# Custom_Keyboard.net
KiCad netlist of a schematic drawn in EasyEDA Pro
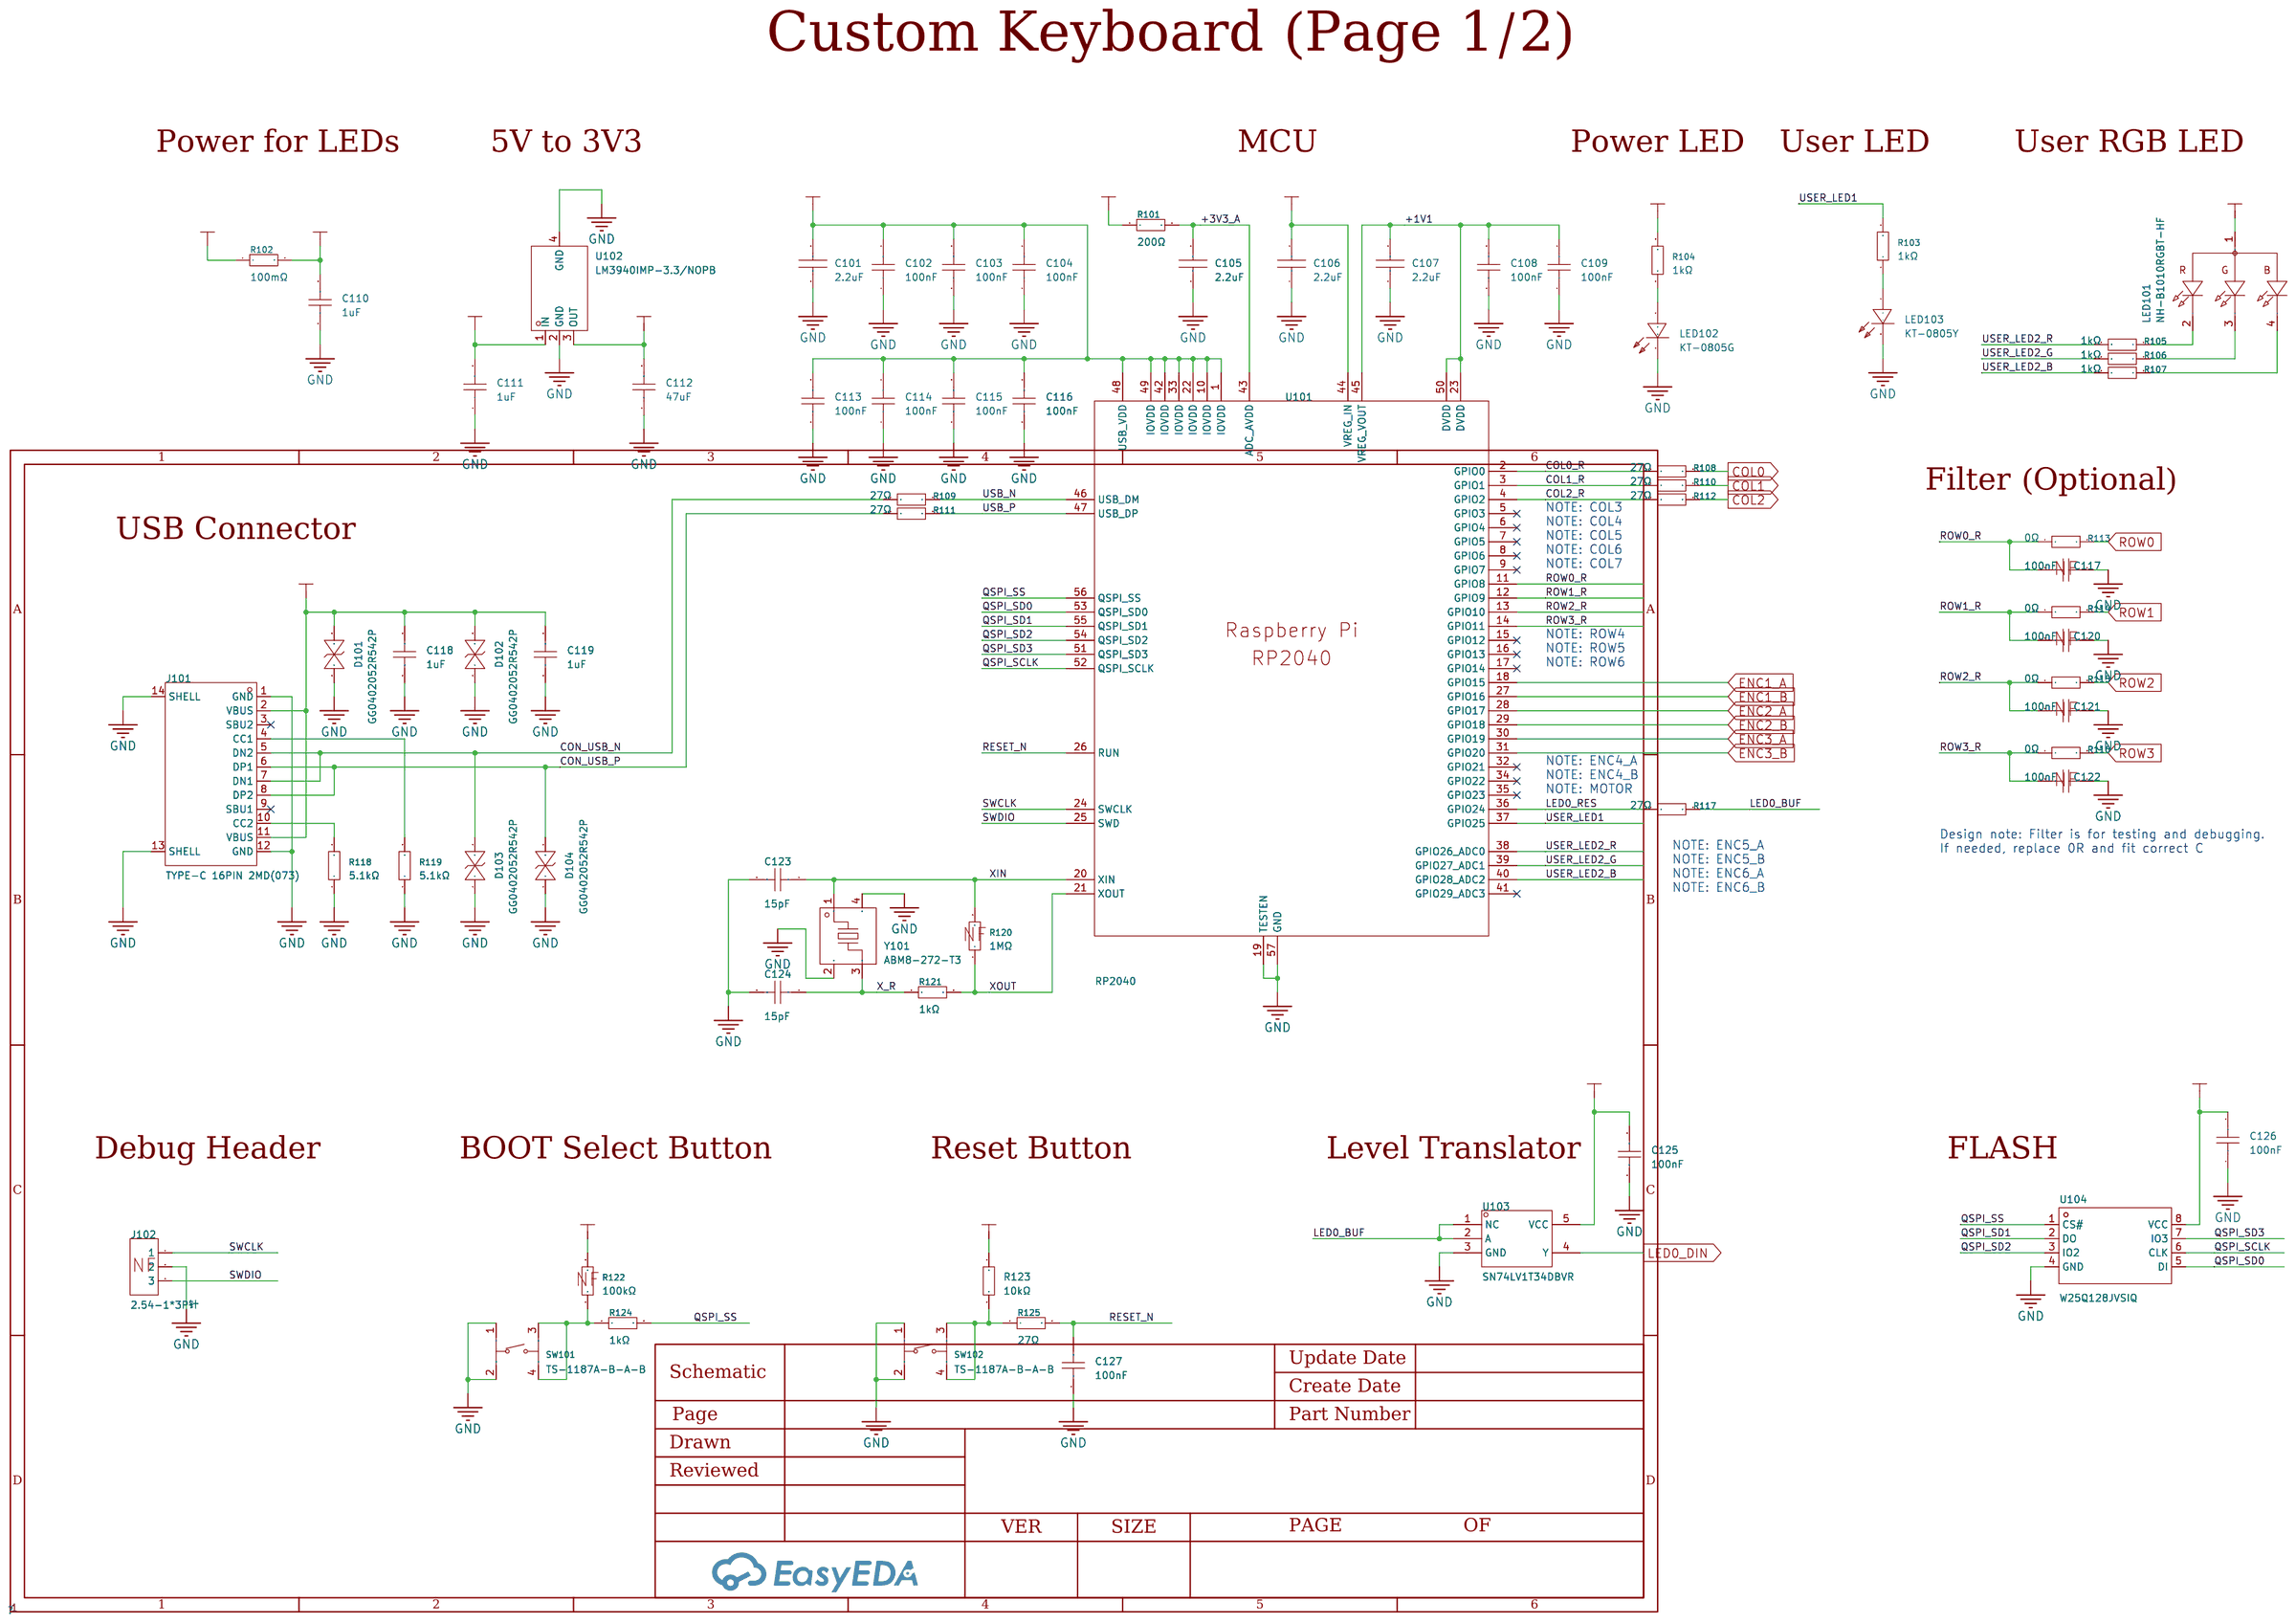
[diagram p0: MCU]
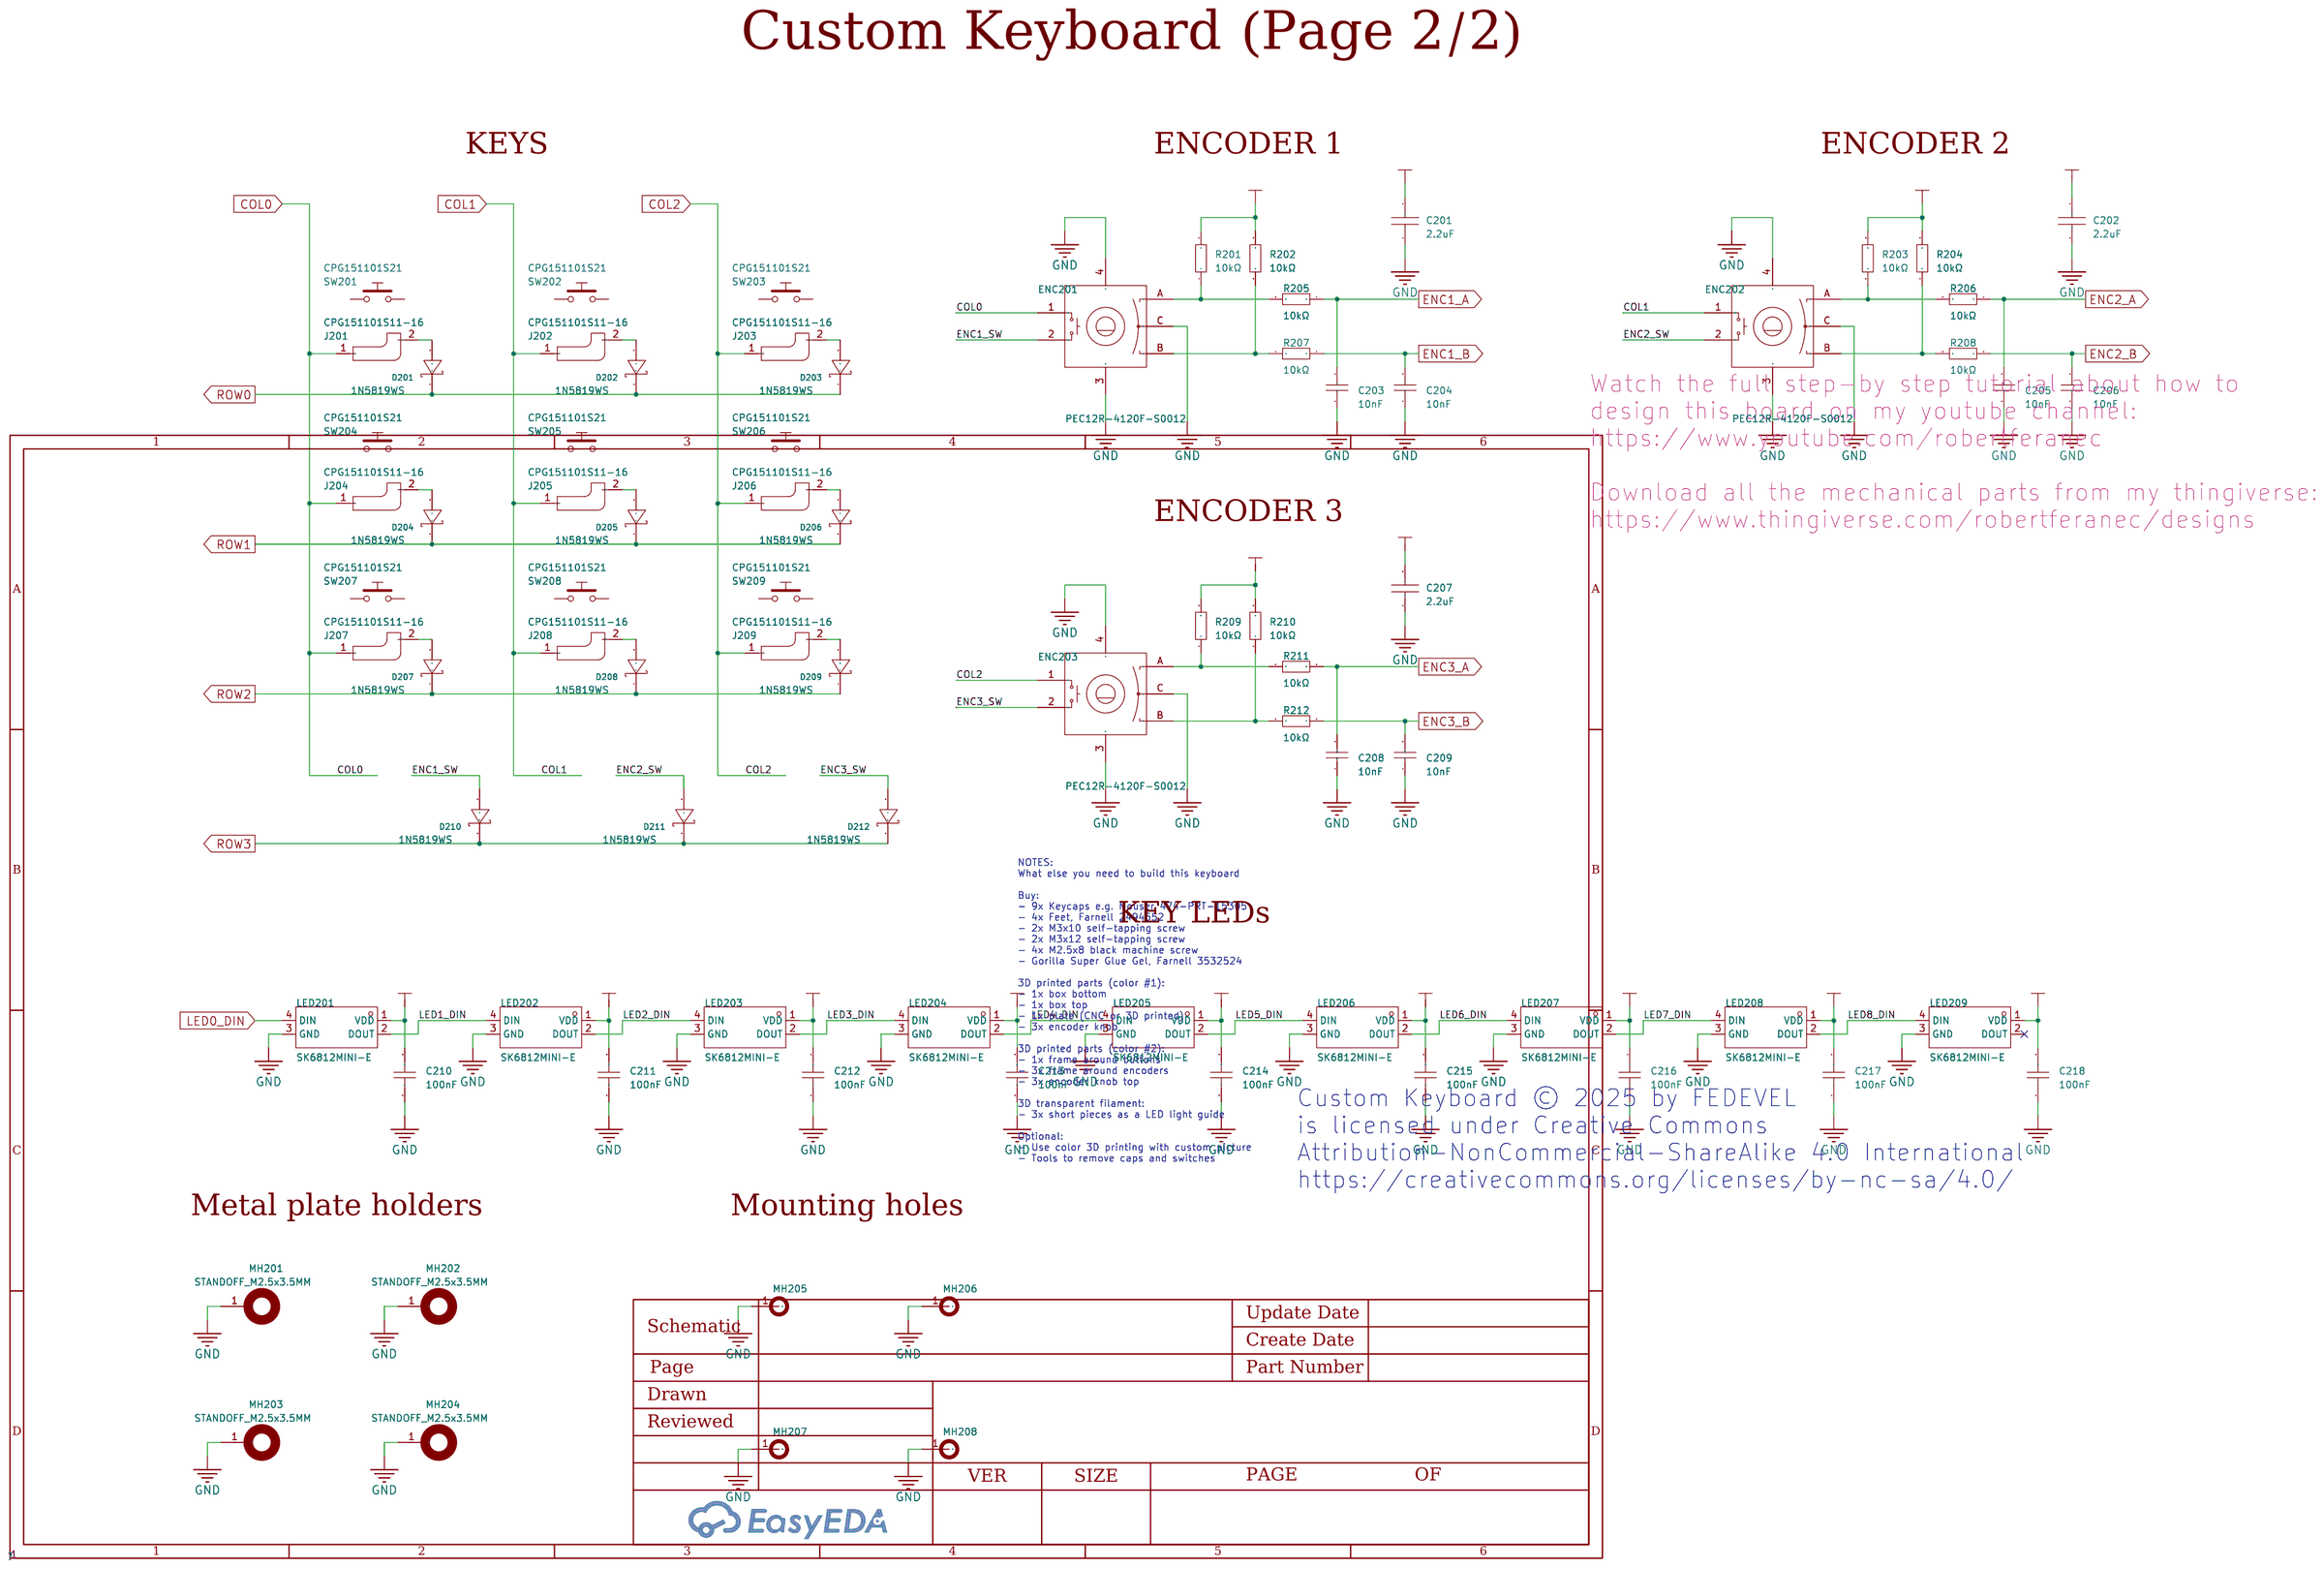
[diagram p1: OTHER]

(export (version "E")
  (design (tool "Eeschema 10.0.6"))
  (components
    (comp (ref "C101")
      (value "2.2uF")
      (footprint "easyedapro:C0402")
      (fields
        (field (name "Manufacturer Part") "CL05A225MQ5NSNC")
        (field (name "Manufacturer") "SAMSUNG(三星)")
      )
      (libsource (lib "easyedapro") (part "CL05A225MQ5NSNC"))
    )
    (comp (ref "C102")
      (value "100nF")
      (footprint "easyedapro:C0402")
      (fields
        (field (name "Manufacturer Part") "CL05B104KO5NNNC")
        (field (name "Manufacturer") "SAMSUNG(三星)")
      )
      (libsource (lib "easyedapro") (part "CL05B104KO5NNNC"))
    )
    (comp (ref "C103")
      (value "100nF")
      (footprint "easyedapro:C0402")
      (fields
        (field (name "Manufacturer Part") "CL05B104KO5NNNC")
        (field (name "Manufacturer") "SAMSUNG(三星)")
      )
      (libsource (lib "easyedapro") (part "CL05B104KO5NNNC"))
    )
    (comp (ref "C104")
      (value "100nF")
      (footprint "easyedapro:C0402")
      (fields
        (field (name "Manufacturer Part") "CL05B104KO5NNNC")
        (field (name "Manufacturer") "SAMSUNG(三星)")
      )
      (libsource (lib "easyedapro") (part "CL05B104KO5NNNC"))
    )
    (comp (ref "C105")
      (value "2.2uF")
      (footprint "easyedapro:C0402")
      (fields
        (field (name "Manufacturer Part") "CL05A225MQ5NSNC")
        (field (name "Manufacturer") "SAMSUNG(三星)")
      )
      (libsource (lib "easyedapro") (part "CL05A225MQ5NSNC"))
    )
    (comp (ref "C106")
      (value "2.2uF")
      (footprint "easyedapro:C0402")
      (fields
        (field (name "Manufacturer Part") "CL05A225MQ5NSNC")
        (field (name "Manufacturer") "SAMSUNG(三星)")
      )
      (libsource (lib "easyedapro") (part "CL05A225MQ5NSNC"))
    )
    (comp (ref "C107")
      (value "2.2uF")
      (footprint "easyedapro:C0402")
      (fields
        (field (name "Manufacturer Part") "CL05A225MQ5NSNC")
        (field (name "Manufacturer") "SAMSUNG(三星)")
      )
      (libsource (lib "easyedapro") (part "CL05A225MQ5NSNC"))
    )
    (comp (ref "C108")
      (value "100nF")
      (footprint "easyedapro:C0402")
      (fields
        (field (name "Manufacturer Part") "CL05B104KO5NNNC")
        (field (name "Manufacturer") "SAMSUNG(三星)")
      )
      (libsource (lib "easyedapro") (part "CL05B104KO5NNNC"))
    )
    (comp (ref "C109")
      (value "100nF")
      (footprint "easyedapro:C0402")
      (fields
        (field (name "Manufacturer Part") "CL05B104KO5NNNC")
        (field (name "Manufacturer") "SAMSUNG(三星)")
      )
      (libsource (lib "easyedapro") (part "CL05B104KO5NNNC"))
    )
    (comp (ref "C110")
      (value "1uF")
      (footprint "easyedapro:C0402")
      (fields
        (field (name "Manufacturer Part") "CL05A105KA5NQNC")
        (field (name "Manufacturer") "SAMSUNG(三星)")
      )
      (libsource (lib "easyedapro") (part "CL05A105KA5NQNC"))
    )
    (comp (ref "C111")
      (value "1uF")
      (footprint "easyedapro:C0402")
      (fields
        (field (name "Manufacturer Part") "CL05A105KA5NQNC")
        (field (name "Manufacturer") "SAMSUNG(三星)")
      )
      (libsource (lib "easyedapro") (part "CL05A105KA5NQNC"))
    )
    (comp (ref "C112")
      (value "47uF")
      (footprint "easyedapro:C1206")
      (fields
        (field (name "Manufacturer Part") "CL31A476MPHNNNE")
        (field (name "Manufacturer") "SAMSUNG(三星)")
      )
      (libsource (lib "easyedapro") (part "CL31A476MPHNNNE"))
    )
    (comp (ref "C113")
      (value "100nF")
      (footprint "easyedapro:C0402")
      (fields
        (field (name "Manufacturer Part") "CL05B104KO5NNNC")
        (field (name "Manufacturer") "SAMSUNG(三星)")
      )
      (libsource (lib "easyedapro") (part "CL05B104KO5NNNC"))
    )
    (comp (ref "C114")
      (value "100nF")
      (footprint "easyedapro:C0402")
      (fields
        (field (name "Manufacturer Part") "CL05B104KO5NNNC")
        (field (name "Manufacturer") "SAMSUNG(三星)")
      )
      (libsource (lib "easyedapro") (part "CL05B104KO5NNNC"))
    )
    (comp (ref "C115")
      (value "100nF")
      (footprint "easyedapro:C0402")
      (fields
        (field (name "Manufacturer Part") "CL05B104KO5NNNC")
        (field (name "Manufacturer") "SAMSUNG(三星)")
      )
      (libsource (lib "easyedapro") (part "CL05B104KO5NNNC"))
    )
    (comp (ref "C116")
      (value "100nF")
      (footprint "easyedapro:C0402")
      (fields
        (field (name "Manufacturer Part") "CL05B104KO5NNNC")
        (field (name "Manufacturer") "SAMSUNG(三星)")
      )
      (libsource (lib "easyedapro") (part "CL05B104KO5NNNC"))
    )
    (comp (ref "C117")
      (value "100nF")
      (footprint "easyedapro:C0402")
      (fields
        (field (name "Manufacturer Part") "CL05B104KO5NNNC")
        (field (name "Manufacturer") "SAMSUNG(三星)")
      )
      (libsource (lib "easyedapro") (part "CL05B104KO5NNNC"))
    )
    (comp (ref "C118")
      (value "1uF")
      (footprint "easyedapro:C0402")
      (fields
        (field (name "Manufacturer Part") "CL05A105KA5NQNC")
        (field (name "Manufacturer") "SAMSUNG(三星)")
      )
      (libsource (lib "easyedapro") (part "CL05A105KA5NQNC"))
    )
    (comp (ref "C119")
      (value "1uF")
      (footprint "easyedapro:C0402")
      (fields
        (field (name "Manufacturer Part") "CL05A105KA5NQNC")
        (field (name "Manufacturer") "SAMSUNG(三星)")
      )
      (libsource (lib "easyedapro") (part "CL05A105KA5NQNC"))
    )
    (comp (ref "C120")
      (value "100nF")
      (footprint "easyedapro:C0402")
      (fields
        (field (name "Manufacturer Part") "CL05B104KO5NNNC")
        (field (name "Manufacturer") "SAMSUNG(三星)")
      )
      (libsource (lib "easyedapro") (part "CL05B104KO5NNNC"))
    )
    (comp (ref "C121")
      (value "100nF")
      (footprint "easyedapro:C0402")
      (fields
        (field (name "Manufacturer Part") "CL05B104KO5NNNC")
        (field (name "Manufacturer") "SAMSUNG(三星)")
      )
      (libsource (lib "easyedapro") (part "CL05B104KO5NNNC"))
    )
    (comp (ref "C122")
      (value "100nF")
      (footprint "easyedapro:C0402")
      (fields
        (field (name "Manufacturer Part") "CL05B104KO5NNNC")
        (field (name "Manufacturer") "SAMSUNG(三星)")
      )
      (libsource (lib "easyedapro") (part "CL05B104KO5NNNC"))
    )
    (comp (ref "C123")
      (value "15pF")
      (footprint "easyedapro:C0402")
      (fields
        (field (name "Manufacturer Part") "CL05C150JB5NNNC")
        (field (name "Manufacturer") "SAMSUNG(三星)")
      )
      (libsource (lib "easyedapro") (part "CL05C150JB5NNNC"))
    )
    (comp (ref "C124")
      (value "15pF")
      (footprint "easyedapro:C0402")
      (fields
        (field (name "Manufacturer Part") "CL05C150JB5NNNC")
        (field (name "Manufacturer") "SAMSUNG(三星)")
      )
      (libsource (lib "easyedapro") (part "CL05C150JB5NNNC"))
    )
    (comp (ref "C125")
      (value "100nF")
      (footprint "easyedapro:C0402")
      (fields
        (field (name "Manufacturer Part") "CL05B104KO5NNNC")
        (field (name "Manufacturer") "SAMSUNG(三星)")
      )
      (libsource (lib "easyedapro") (part "CL05B104KO5NNNC"))
    )
    (comp (ref "C126")
      (value "100nF")
      (footprint "easyedapro:C0402")
      (fields
        (field (name "Manufacturer Part") "CL05B104KO5NNNC")
        (field (name "Manufacturer") "SAMSUNG(三星)")
      )
      (libsource (lib "easyedapro") (part "CL05B104KO5NNNC"))
    )
    (comp (ref "C127")
      (value "100nF")
      (footprint "easyedapro:C0402")
      (fields
        (field (name "Manufacturer Part") "CL05B104KO5NNNC")
        (field (name "Manufacturer") "SAMSUNG(三星)")
      )
      (libsource (lib "easyedapro") (part "CL05B104KO5NNNC"))
    )
    (comp (ref "D101")
      (value "GG0402052R542P")
      (footprint "easyedapro:D0402-BI")
      (fields (field (name "Manufacturer") "Kyocera AVX"))
      (libsource (lib "easyedapro") (part "GG0402052R542P"))
    )
    (comp (ref "D102")
      (value "GG0402052R542P")
      (footprint "easyedapro:D0402-BI")
      (fields (field (name "Manufacturer") "Kyocera AVX"))
      (libsource (lib "easyedapro") (part "GG0402052R542P"))
    )
    (comp (ref "D103")
      (value "GG0402052R542P")
      (footprint "easyedapro:D0402-BI")
      (fields (field (name "Manufacturer") "Kyocera AVX"))
      (libsource (lib "easyedapro") (part "GG0402052R542P"))
    )
    (comp (ref "D104")
      (value "GG0402052R542P")
      (footprint "easyedapro:D0402-BI")
      (fields (field (name "Manufacturer") "Kyocera AVX"))
      (libsource (lib "easyedapro") (part "GG0402052R542P"))
    )
    (comp (ref "J101")
      (value "TYPE-C 16PIN 2MD(073)")
      (footprint "easyedapro:USB-C-SMD_TYPE-C-6PIN-2MD-073")
      (fields (field (name "Manufacturer") "SHOU HAN(首韩)"))
      (libsource (lib "easyedapro") (part "TYPE-C 16PIN 2MD(073)"))
    )
    (comp (ref "J102")
      (value "2.54-1*3P针")
      (footprint "easyedapro:HDR-TH_3P-P2.54-V-M-1")
      (fields (field (name "Manufacturer") "BOOMELE(博穆精密)"))
      (libsource (lib "easyedapro") (part "Header-Male-2.54_1x3"))
    )
    (comp (ref "LED101")
      (value "NH-B1010RGBT-HF")
      (footprint "easyedapro:LED-ARRAY-SMD_4P-L1.0-W1.0-TR_NH-B1010RGBT_1")
      (fields (field (name "Manufacturer") "国星光电"))
      (libsource (lib "easyedapro") (part "NH-B1010RGBT-HF_RF_v1.0"))
    )
    (comp (ref "LED102")
      (value "KT-0805G")
      (footprint "easyedapro:LED0805-R-RD")
      (fields (field (name "Manufacturer") "KENTO"))
      (libsource (lib "easyedapro") (part "0805G (Green)"))
    )
    (comp (ref "LED103")
      (value "KT-0805Y")
      (footprint "easyedapro:LED0805-R-RD")
      (fields (field (name "Manufacturer") "KENTO"))
      (libsource (lib "easyedapro") (part "17-21SUYC/TR8"))
    )
    (comp (ref "R101")
      (value "200Ω")
      (footprint "easyedapro:R0402")
      (fields
        (field (name "Manufacturer Part") "0402WGF2000TCE")
        (field (name "Manufacturer") "UNI-ROYAL(厚声)")
      )
      (libsource (lib "easyedapro") (part "0402WGF2000TCE"))
    )
    (comp (ref "R102")
      (value "100mΩ")
      (footprint "easyedapro:R1206")
      (fields
        (field (name "Manufacturer Part") "1206W4F100LT5E")
        (field (name "Manufacturer") "UNI-ROYAL(厚声)")
      )
      (libsource (lib "easyedapro") (part "1206W4F100LT5E"))
    )
    (comp (ref "R103")
      (value "1kΩ")
      (footprint "easyedapro:R0402")
      (fields
        (field (name "Manufacturer Part") "0402WGF1001TCE")
        (field (name "Manufacturer") "UNI-ROYAL(厚声)")
      )
      (libsource (lib "easyedapro") (part "0402WGF1001TCE"))
    )
    (comp (ref "R104")
      (value "1kΩ")
      (footprint "easyedapro:R0402")
      (fields
        (field (name "Manufacturer Part") "0402WGF1001TCE")
        (field (name "Manufacturer") "UNI-ROYAL(厚声)")
      )
      (libsource (lib "easyedapro") (part "0402WGF1001TCE"))
    )
    (comp (ref "R105")
      (value "1kΩ")
      (footprint "easyedapro:R0402")
      (fields
        (field (name "Manufacturer Part") "0402WGF1001TCE")
        (field (name "Manufacturer") "UNI-ROYAL(厚声)")
      )
      (libsource (lib "easyedapro") (part "0402WGF1001TCE"))
    )
    (comp (ref "R106")
      (value "1kΩ")
      (footprint "easyedapro:R0402")
      (fields
        (field (name "Manufacturer Part") "0402WGF1001TCE")
        (field (name "Manufacturer") "UNI-ROYAL(厚声)")
      )
      (libsource (lib "easyedapro") (part "0402WGF1001TCE"))
    )
    (comp (ref "R107")
      (value "1kΩ")
      (footprint "easyedapro:R0402")
      (fields
        (field (name "Manufacturer Part") "0402WGF1001TCE")
        (field (name "Manufacturer") "UNI-ROYAL(厚声)")
      )
      (libsource (lib "easyedapro") (part "0402WGF1001TCE"))
    )
    (comp (ref "R108")
      (value "27Ω")
      (footprint "easyedapro:R0402")
      (fields
        (field (name "Manufacturer Part") "0402WGF270JTCE")
        (field (name "Manufacturer") "UNI-ROYAL(厚声)")
      )
      (libsource (lib "easyedapro") (part "0402WGF270JTCE"))
    )
    (comp (ref "R109")
      (value "27Ω")
      (footprint "easyedapro:R0402")
      (fields
        (field (name "Manufacturer Part") "0402WGF270JTCE")
        (field (name "Manufacturer") "UNI-ROYAL(厚声)")
      )
      (libsource (lib "easyedapro") (part "0402WGF270JTCE"))
    )
    (comp (ref "R110")
      (value "27Ω")
      (footprint "easyedapro:R0402")
      (fields
        (field (name "Manufacturer Part") "0402WGF270JTCE")
        (field (name "Manufacturer") "UNI-ROYAL(厚声)")
      )
      (libsource (lib "easyedapro") (part "0402WGF270JTCE"))
    )
    (comp (ref "R111")
      (value "27Ω")
      (footprint "easyedapro:R0402")
      (fields
        (field (name "Manufacturer Part") "0402WGF270JTCE")
        (field (name "Manufacturer") "UNI-ROYAL(厚声)")
      )
      (libsource (lib "easyedapro") (part "0402WGF270JTCE"))
    )
    (comp (ref "R112")
      (value "27Ω")
      (footprint "easyedapro:R0402")
      (fields
        (field (name "Manufacturer Part") "0402WGF270JTCE")
        (field (name "Manufacturer") "UNI-ROYAL(厚声)")
      )
      (libsource (lib "easyedapro") (part "0402WGF270JTCE"))
    )
    (comp (ref "R113")
      (value "0Ω")
      (footprint "easyedapro:R0402")
      (fields
        (field (name "Manufacturer Part") "0402WGF0000TCE")
        (field (name "Manufacturer") "UNI-ROYAL(厚声)")
      )
      (libsource (lib "easyedapro") (part "0402WGF0000TCE"))
    )
    (comp (ref "R114")
      (value "0Ω")
      (footprint "easyedapro:R0402")
      (fields
        (field (name "Manufacturer Part") "0402WGF0000TCE")
        (field (name "Manufacturer") "UNI-ROYAL(厚声)")
      )
      (libsource (lib "easyedapro") (part "0402WGF0000TCE"))
    )
    (comp (ref "R115")
      (value "0Ω")
      (footprint "easyedapro:R0402")
      (fields
        (field (name "Manufacturer Part") "0402WGF0000TCE")
        (field (name "Manufacturer") "UNI-ROYAL(厚声)")
      )
      (libsource (lib "easyedapro") (part "0402WGF0000TCE"))
    )
    (comp (ref "R116")
      (value "0Ω")
      (footprint "easyedapro:R0402")
      (fields
        (field (name "Manufacturer Part") "0402WGF0000TCE")
        (field (name "Manufacturer") "UNI-ROYAL(厚声)")
      )
      (libsource (lib "easyedapro") (part "0402WGF0000TCE"))
    )
    (comp (ref "R117")
      (value "27Ω")
      (footprint "easyedapro:R0402")
      (fields
        (field (name "Manufacturer Part") "0402WGF270JTCE")
        (field (name "Manufacturer") "UNI-ROYAL(厚声)")
      )
      (libsource (lib "easyedapro") (part "0402WGF270JTCE"))
    )
    (comp (ref "R118")
      (value "5.1kΩ")
      (footprint "easyedapro:R0402")
      (fields
        (field (name "Manufacturer Part") "0402WGF5101TCE")
        (field (name "Manufacturer") "UNI-ROYAL(厚声)")
      )
      (libsource (lib "easyedapro") (part "0402WGF5101TCE"))
    )
    (comp (ref "R119")
      (value "5.1kΩ")
      (footprint "easyedapro:R0402")
      (fields
        (field (name "Manufacturer Part") "0402WGF5101TCE")
        (field (name "Manufacturer") "UNI-ROYAL(厚声)")
      )
      (libsource (lib "easyedapro") (part "0402WGF5101TCE"))
    )
    (comp (ref "R120")
      (value "1MΩ")
      (footprint "easyedapro:R0402")
      (fields
        (field (name "Manufacturer Part") "0402WGF1004TCE")
        (field (name "Manufacturer") "UNI-ROYAL(厚声)")
      )
      (libsource (lib "easyedapro") (part "0402WGF1004TCE"))
    )
    (comp (ref "R121")
      (value "1kΩ")
      (footprint "easyedapro:R0402")
      (fields
        (field (name "Manufacturer Part") "0402WGF1001TCE")
        (field (name "Manufacturer") "UNI-ROYAL(厚声)")
      )
      (libsource (lib "easyedapro") (part "0402WGF1001TCE"))
    )
    (comp (ref "R122")
      (value "100kΩ")
      (footprint "easyedapro:R0402")
      (fields
        (field (name "Manufacturer Part") "0402WGF1003TCE")
        (field (name "Manufacturer") "UNI-ROYAL(厚声)")
      )
      (libsource (lib "easyedapro") (part "0402WGF1003TCE"))
    )
    (comp (ref "R123")
      (value "10kΩ")
      (footprint "easyedapro:R0402")
      (fields
        (field (name "Manufacturer Part") "0402WGF1002TCE")
        (field (name "Manufacturer") "UNI-ROYAL(厚声)")
      )
      (libsource (lib "easyedapro") (part "0402WGF1002TCE"))
    )
    (comp (ref "R124")
      (value "1kΩ")
      (footprint "easyedapro:R0402")
      (fields
        (field (name "Manufacturer Part") "0402WGF1001TCE")
        (field (name "Manufacturer") "UNI-ROYAL(厚声)")
      )
      (libsource (lib "easyedapro") (part "0402WGF1001TCE"))
    )
    (comp (ref "R125")
      (value "27Ω")
      (footprint "easyedapro:R0402")
      (fields
        (field (name "Manufacturer Part") "0402WGF270JTCE")
        (field (name "Manufacturer") "UNI-ROYAL(厚声)")
      )
      (libsource (lib "easyedapro") (part "0402WGF270JTCE"))
    )
    (comp (ref "SW101")
      (value "TS-1187A-B-A-B")
      (footprint "easyedapro:SW-SMD_4P-L5.1-W5.1-P3.70-LS6.5-TL-2")
      (fields (field (name "Manufacturer") "XKB Connectivity(中国星坤)"))
      (libsource (lib "easyedapro") (part "TS-1187A-B-A-B"))
    )
    (comp (ref "SW102")
      (value "TS-1187A-B-A-B")
      (footprint "easyedapro:SW-SMD_4P-L5.1-W5.1-P3.70-LS6.5-TL-2")
      (fields (field (name "Manufacturer") "XKB Connectivity(中国星坤)"))
      (libsource (lib "easyedapro") (part "TS-1187A-B-A-B"))
    )
    (comp (ref "U101")
      (value "RP2040")
      (footprint "easyedapro:LQFN-56_L7.0-W7.0-P0.4-EP_1")
      (fields (field (name "Manufacturer") "Raspberry Pi(树莓派)"))
      (libsource (lib "easyedapro") (part "RP2040_C2040_RF_v1.0"))
    )
    (comp (ref "U102")
      (value "LM3940IMP-3.3/NOPB")
      (footprint "easyedapro:SOT-223_L6.5-W3.5-P2.30-LS7.0-BR")
      (fields (field (name "Manufacturer") "TI(德州仪器)"))
      (libsource (lib "easyedapro") (part "LM3940IMP-3.3/NOPB"))
    )
    (comp (ref "U103")
      (value "SN74LV1T34DBVR")
      (footprint "easyedapro:SOT-23-5_L2.9-W1.6-P0.95-LS2.8-BR")
      (fields (field (name "Manufacturer") "TI(德州仪器)"))
      (libsource (lib "easyedapro") (part "SN74LV1T34DBVR_RF_v1.0"))
    )
    (comp (ref "U104")
      (value "W25Q128JVSIQ")
      (footprint "easyedapro:SOIC-8_L5.3-W5.3-P1.27-LS8.0-BL")
      (fields (field (name "Manufacturer") "WINBOND(华邦)"))
      (libsource (lib "easyedapro") (part "W25Q128JVSIQTR"))
    )
    (comp (ref "Y101")
      (value "ABM8-272-T3")
      (footprint "easyedapro:CRYSTAL-SMD_4P-L3.2-W2.5-BL")
      (fields (field (name "Manufacturer") "ABRACON"))
      (libsource (lib "easyedapro") (part "ABM8-272-T3_C20625731"))
    )
    (comp (ref "C201")
      (value "2.2uF")
      (footprint "easyedapro:C0402")
      (fields
        (field (name "Manufacturer Part") "CL05A225MQ5NSNC")
        (field (name "Manufacturer") "SAMSUNG(三星)")
      )
      (libsource (lib "easyedapro") (part "CL05A225MQ5NSNC"))
    )
    (comp (ref "C202")
      (value "2.2uF")
      (footprint "easyedapro:C0402")
      (fields
        (field (name "Manufacturer Part") "CL05A225MQ5NSNC")
        (field (name "Manufacturer") "SAMSUNG(三星)")
      )
      (libsource (lib "easyedapro") (part "CL05A225MQ5NSNC"))
    )
    (comp (ref "C203")
      (value "10nF")
      (footprint "easyedapro:C0402")
      (fields
        (field (name "Manufacturer Part") "CL05B103KB5NNNC")
        (field (name "Manufacturer") "SAMSUNG(三星)")
      )
      (libsource (lib "easyedapro") (part "CL05B103KB5NNNC"))
    )
    (comp (ref "C204")
      (value "10nF")
      (footprint "easyedapro:C0402")
      (fields
        (field (name "Manufacturer Part") "CL05B103KB5NNNC")
        (field (name "Manufacturer") "SAMSUNG(三星)")
      )
      (libsource (lib "easyedapro") (part "CL05B103KB5NNNC"))
    )
    (comp (ref "C205")
      (value "10nF")
      (footprint "easyedapro:C0402")
      (fields
        (field (name "Manufacturer Part") "CL05B103KB5NNNC")
        (field (name "Manufacturer") "SAMSUNG(三星)")
      )
      (libsource (lib "easyedapro") (part "CL05B103KB5NNNC"))
    )
    (comp (ref "C206")
      (value "10nF")
      (footprint "easyedapro:C0402")
      (fields
        (field (name "Manufacturer Part") "CL05B103KB5NNNC")
        (field (name "Manufacturer") "SAMSUNG(三星)")
      )
      (libsource (lib "easyedapro") (part "CL05B103KB5NNNC"))
    )
    (comp (ref "C207")
      (value "2.2uF")
      (footprint "easyedapro:C0402")
      (fields
        (field (name "Manufacturer Part") "CL05A225MQ5NSNC")
        (field (name "Manufacturer") "SAMSUNG(三星)")
      )
      (libsource (lib "easyedapro") (part "CL05A225MQ5NSNC"))
    )
    (comp (ref "C208")
      (value "10nF")
      (footprint "easyedapro:C0402")
      (fields
        (field (name "Manufacturer Part") "CL05B103KB5NNNC")
        (field (name "Manufacturer") "SAMSUNG(三星)")
      )
      (libsource (lib "easyedapro") (part "CL05B103KB5NNNC"))
    )
    (comp (ref "C209")
      (value "10nF")
      (footprint "easyedapro:C0402")
      (fields
        (field (name "Manufacturer Part") "CL05B103KB5NNNC")
        (field (name "Manufacturer") "SAMSUNG(三星)")
      )
      (libsource (lib "easyedapro") (part "CL05B103KB5NNNC"))
    )
    (comp (ref "C210")
      (value "100nF")
      (footprint "easyedapro:C0402")
      (fields
        (field (name "Manufacturer Part") "CL05B104KO5NNNC")
        (field (name "Manufacturer") "SAMSUNG(三星)")
      )
      (libsource (lib "easyedapro") (part "CL05B104KO5NNNC"))
    )
    (comp (ref "C211")
      (value "100nF")
      (footprint "easyedapro:C0402")
      (fields
        (field (name "Manufacturer Part") "CL05B104KO5NNNC")
        (field (name "Manufacturer") "SAMSUNG(三星)")
      )
      (libsource (lib "easyedapro") (part "CL05B104KO5NNNC"))
    )
    (comp (ref "C212")
      (value "100nF")
      (footprint "easyedapro:C0402")
      (fields
        (field (name "Manufacturer Part") "CL05B104KO5NNNC")
        (field (name "Manufacturer") "SAMSUNG(三星)")
      )
      (libsource (lib "easyedapro") (part "CL05B104KO5NNNC"))
    )
    (comp (ref "C213")
      (value "100nF")
      (footprint "easyedapro:C0402")
      (fields
        (field (name "Manufacturer Part") "CL05B104KO5NNNC")
        (field (name "Manufacturer") "SAMSUNG(三星)")
      )
      (libsource (lib "easyedapro") (part "CL05B104KO5NNNC"))
    )
    (comp (ref "C214")
      (value "100nF")
      (footprint "easyedapro:C0402")
      (fields
        (field (name "Manufacturer Part") "CL05B104KO5NNNC")
        (field (name "Manufacturer") "SAMSUNG(三星)")
      )
      (libsource (lib "easyedapro") (part "CL05B104KO5NNNC"))
    )
    (comp (ref "C215")
      (value "100nF")
      (footprint "easyedapro:C0402")
      (fields
        (field (name "Manufacturer Part") "CL05B104KO5NNNC")
        (field (name "Manufacturer") "SAMSUNG(三星)")
      )
      (libsource (lib "easyedapro") (part "CL05B104KO5NNNC"))
    )
    (comp (ref "C216")
      (value "100nF")
      (footprint "easyedapro:C0402")
      (fields
        (field (name "Manufacturer Part") "CL05B104KO5NNNC")
        (field (name "Manufacturer") "SAMSUNG(三星)")
      )
      (libsource (lib "easyedapro") (part "CL05B104KO5NNNC"))
    )
    (comp (ref "C217")
      (value "100nF")
      (footprint "easyedapro:C0402")
      (fields
        (field (name "Manufacturer Part") "CL05B104KO5NNNC")
        (field (name "Manufacturer") "SAMSUNG(三星)")
      )
      (libsource (lib "easyedapro") (part "CL05B104KO5NNNC"))
    )
    (comp (ref "C218")
      (value "100nF")
      (footprint "easyedapro:C0402")
      (fields
        (field (name "Manufacturer Part") "CL05B104KO5NNNC")
        (field (name "Manufacturer") "SAMSUNG(三星)")
      )
      (libsource (lib "easyedapro") (part "CL05B104KO5NNNC"))
    )
    (comp (ref "D201")
      (value "1N5819WS")
      (footprint "easyedapro:SOD-323_L1.8-W1.3-LS2.5-RD")
      (description "Forward Voltage (Vf@If):600mV@1A Reverse Voltage (Vr):40V Average Rectified Current (Io):1A")
      (fields (field (name "Manufacturer") "Hottech(合科泰)"))
      (libsource (lib "easyedapro") (part "1N5819WS"))
    )
    (comp (ref "D202")
      (value "1N5819WS")
      (footprint "easyedapro:SOD-323_L1.8-W1.3-LS2.5-RD")
      (description "Forward Voltage (Vf@If):600mV@1A Reverse Voltage (Vr):40V Average Rectified Current (Io):1A")
      (fields (field (name "Manufacturer") "Hottech(合科泰)"))
      (libsource (lib "easyedapro") (part "1N5819WS"))
    )
    (comp (ref "D203")
      (value "1N5819WS")
      (footprint "easyedapro:SOD-323_L1.8-W1.3-LS2.5-RD")
      (description "Forward Voltage (Vf@If):600mV@1A Reverse Voltage (Vr):40V Average Rectified Current (Io):1A")
      (fields (field (name "Manufacturer") "Hottech(合科泰)"))
      (libsource (lib "easyedapro") (part "1N5819WS"))
    )
    (comp (ref "D204")
      (value "1N5819WS")
      (footprint "easyedapro:SOD-323_L1.8-W1.3-LS2.5-RD")
      (description "Forward Voltage (Vf@If):600mV@1A Reverse Voltage (Vr):40V Average Rectified Current (Io):1A")
      (fields (field (name "Manufacturer") "Hottech(合科泰)"))
      (libsource (lib "easyedapro") (part "1N5819WS"))
    )
    (comp (ref "D205")
      (value "1N5819WS")
      (footprint "easyedapro:SOD-323_L1.8-W1.3-LS2.5-RD")
      (description "Forward Voltage (Vf@If):600mV@1A Reverse Voltage (Vr):40V Average Rectified Current (Io):1A")
      (fields (field (name "Manufacturer") "Hottech(合科泰)"))
      (libsource (lib "easyedapro") (part "1N5819WS"))
    )
    (comp (ref "D206")
      (value "1N5819WS")
      (footprint "easyedapro:SOD-323_L1.8-W1.3-LS2.5-RD")
      (description "Forward Voltage (Vf@If):600mV@1A Reverse Voltage (Vr):40V Average Rectified Current (Io):1A")
      (fields (field (name "Manufacturer") "Hottech(合科泰)"))
      (libsource (lib "easyedapro") (part "1N5819WS"))
    )
    (comp (ref "D207")
      (value "1N5819WS")
      (footprint "easyedapro:SOD-323_L1.8-W1.3-LS2.5-RD")
      (description "Forward Voltage (Vf@If):600mV@1A Reverse Voltage (Vr):40V Average Rectified Current (Io):1A")
      (fields (field (name "Manufacturer") "Hottech(合科泰)"))
      (libsource (lib "easyedapro") (part "1N5819WS"))
    )
    (comp (ref "D208")
      (value "1N5819WS")
      (footprint "easyedapro:SOD-323_L1.8-W1.3-LS2.5-RD")
      (description "Forward Voltage (Vf@If):600mV@1A Reverse Voltage (Vr):40V Average Rectified Current (Io):1A")
      (fields (field (name "Manufacturer") "Hottech(合科泰)"))
      (libsource (lib "easyedapro") (part "1N5819WS"))
    )
    (comp (ref "D209")
      (value "1N5819WS")
      (footprint "easyedapro:SOD-323_L1.8-W1.3-LS2.5-RD")
      (description "Forward Voltage (Vf@If):600mV@1A Reverse Voltage (Vr):40V Average Rectified Current (Io):1A")
      (fields (field (name "Manufacturer") "Hottech(合科泰)"))
      (libsource (lib "easyedapro") (part "1N5819WS"))
    )
    (comp (ref "D210")
      (value "1N5819WS")
      (footprint "easyedapro:SOD-323_L1.8-W1.3-LS2.5-RD")
      (description "Forward Voltage (Vf@If):600mV@1A Reverse Voltage (Vr):40V Average Rectified Current (Io):1A")
      (fields (field (name "Manufacturer") "Hottech(合科泰)"))
      (libsource (lib "easyedapro") (part "1N5819WS"))
    )
    (comp (ref "D211")
      (value "1N5819WS")
      (footprint "easyedapro:SOD-323_L1.8-W1.3-LS2.5-RD")
      (description "Forward Voltage (Vf@If):600mV@1A Reverse Voltage (Vr):40V Average Rectified Current (Io):1A")
      (fields (field (name "Manufacturer") "Hottech(合科泰)"))
      (libsource (lib "easyedapro") (part "1N5819WS"))
    )
    (comp (ref "D212")
      (value "1N5819WS")
      (footprint "easyedapro:SOD-323_L1.8-W1.3-LS2.5-RD")
      (description "Forward Voltage (Vf@If):600mV@1A Reverse Voltage (Vr):40V Average Rectified Current (Io):1A")
      (fields (field (name "Manufacturer") "Hottech(合科泰)"))
      (libsource (lib "easyedapro") (part "1N5819WS"))
    )
    (comp (ref "ENC201")
      (value "PEC12R-4120F-S0012")
      (footprint "easyedapro:SW-TH_PEC12R-4120F-S0012_1")
      (fields (field (name "Manufacturer") "BOURNS"))
      (libsource (lib "easyedapro") (part "PEC12R-4120F-S0012_RF_v1.0"))
    )
    (comp (ref "ENC202")
      (value "PEC12R-4120F-S0012")
      (footprint "easyedapro:SW-TH_PEC12R-4120F-S0012_1")
      (fields (field (name "Manufacturer") "BOURNS"))
      (libsource (lib "easyedapro") (part "PEC12R-4120F-S0012_RF_v1.0"))
    )
    (comp (ref "ENC203")
      (value "PEC12R-4120F-S0012")
      (footprint "easyedapro:SW-TH_PEC12R-4120F-S0012_1")
      (fields (field (name "Manufacturer") "BOURNS"))
      (libsource (lib "easyedapro") (part "PEC12R-4120F-S0012_RF_v1.0"))
    )
    (comp (ref "J201")
      (value "CPG151101S11-16")
      (footprint "easyedapro:SMD_KEYBOARD-SW_1")
      (fields (field (name "Manufacturer") "Kailh(凯华)"))
      (libsource (lib "easyedapro") (part "CPG151101S11-16_RF_v1.0"))
    )
    (comp (ref "J202")
      (value "CPG151101S11-16")
      (footprint "easyedapro:SMD_KEYBOARD-SW_1")
      (fields (field (name "Manufacturer") "Kailh(凯华)"))
      (libsource (lib "easyedapro") (part "CPG151101S11-16_RF_v1.0"))
    )
    (comp (ref "J203")
      (value "CPG151101S11-16")
      (footprint "easyedapro:SMD_KEYBOARD-SW_1")
      (fields (field (name "Manufacturer") "Kailh(凯华)"))
      (libsource (lib "easyedapro") (part "CPG151101S11-16_RF_v1.0"))
    )
    (comp (ref "J204")
      (value "CPG151101S11-16")
      (footprint "easyedapro:SMD_KEYBOARD-SW_1")
      (fields (field (name "Manufacturer") "Kailh(凯华)"))
      (libsource (lib "easyedapro") (part "CPG151101S11-16_RF_v1.0"))
    )
    (comp (ref "J205")
      (value "CPG151101S11-16")
      (footprint "easyedapro:SMD_KEYBOARD-SW_1")
      (fields (field (name "Manufacturer") "Kailh(凯华)"))
      (libsource (lib "easyedapro") (part "CPG151101S11-16_RF_v1.0"))
    )
    (comp (ref "J206")
      (value "CPG151101S11-16")
      (footprint "easyedapro:SMD_KEYBOARD-SW_1")
      (fields (field (name "Manufacturer") "Kailh(凯华)"))
      (libsource (lib "easyedapro") (part "CPG151101S11-16_RF_v1.0"))
    )
    (comp (ref "J207")
      (value "CPG151101S11-16")
      (footprint "easyedapro:SMD_KEYBOARD-SW_1")
      (fields (field (name "Manufacturer") "Kailh(凯华)"))
      (libsource (lib "easyedapro") (part "CPG151101S11-16_RF_v1.0"))
    )
    (comp (ref "J208")
      (value "CPG151101S11-16")
      (footprint "easyedapro:SMD_KEYBOARD-SW_1")
      (fields (field (name "Manufacturer") "Kailh(凯华)"))
      (libsource (lib "easyedapro") (part "CPG151101S11-16_RF_v1.0"))
    )
    (comp (ref "J209")
      (value "CPG151101S11-16")
      (footprint "easyedapro:SMD_KEYBOARD-SW_1")
      (fields (field (name "Manufacturer") "Kailh(凯华)"))
      (libsource (lib "easyedapro") (part "CPG151101S11-16_RF_v1.0"))
    )
    (comp (ref "LED201")
      (value "SK6812MINI-E")
      (footprint "easyedapro:LED-SMD_L3.2-W2.8-TR")
      (fields (field (name "Manufacturer") "欧思科光电"))
      (libsource (lib "easyedapro") (part "SK6812MINI-E_C5149201"))
    )
    (comp (ref "LED202")
      (value "SK6812MINI-E")
      (footprint "easyedapro:LED-SMD_L3.2-W2.8-TR")
      (fields (field (name "Manufacturer") "欧思科光电"))
      (libsource (lib "easyedapro") (part "SK6812MINI-E_C5149201"))
    )
    (comp (ref "LED203")
      (value "SK6812MINI-E")
      (footprint "easyedapro:LED-SMD_L3.2-W2.8-TR")
      (fields (field (name "Manufacturer") "欧思科光电"))
      (libsource (lib "easyedapro") (part "SK6812MINI-E_C5149201"))
    )
    (comp (ref "LED204")
      (value "SK6812MINI-E")
      (footprint "easyedapro:LED-SMD_L3.2-W2.8-TR")
      (fields (field (name "Manufacturer") "欧思科光电"))
      (libsource (lib "easyedapro") (part "SK6812MINI-E_C5149201"))
    )
    (comp (ref "LED205")
      (value "SK6812MINI-E")
      (footprint "easyedapro:LED-SMD_L3.2-W2.8-TR")
      (fields (field (name "Manufacturer") "欧思科光电"))
      (libsource (lib "easyedapro") (part "SK6812MINI-E_C5149201"))
    )
    (comp (ref "LED206")
      (value "SK6812MINI-E")
      (footprint "easyedapro:LED-SMD_L3.2-W2.8-TR")
      (fields (field (name "Manufacturer") "欧思科光电"))
      (libsource (lib "easyedapro") (part "SK6812MINI-E_C5149201"))
    )
    (comp (ref "LED207")
      (value "SK6812MINI-E")
      (footprint "easyedapro:LED-SMD_L3.2-W2.8-TR")
      (fields (field (name "Manufacturer") "欧思科光电"))
      (libsource (lib "easyedapro") (part "SK6812MINI-E_C5149201"))
    )
    (comp (ref "LED208")
      (value "SK6812MINI-E")
      (footprint "easyedapro:LED-SMD_L3.2-W2.8-TR")
      (fields (field (name "Manufacturer") "欧思科光电"))
      (libsource (lib "easyedapro") (part "SK6812MINI-E_C5149201"))
    )
    (comp (ref "LED209")
      (value "SK6812MINI-E")
      (footprint "easyedapro:LED-SMD_L3.2-W2.8-TR")
      (fields (field (name "Manufacturer") "欧思科光电"))
      (libsource (lib "easyedapro") (part "SK6812MINI-E_C5149201"))
    )
    (comp (ref "MH201")
      (value "STANDOFF_M2.5x3.5MM")
      (footprint "easyedapro:STANDOFF_M2.5x3.5MM_RF_v1.0")
      (description "Standoff, Steel, M2.5, Hex Female-Female, 3.5 mm, 4.9 mm, WA-SMSI Series")
      (fields (field (name "Manufacturer") "WURTH ELEKTRONIK"))
      (libsource (lib "easyedapro") (part "9774035151R_RF_v1.0"))
    )
    (comp (ref "MH202")
      (value "STANDOFF_M2.5x3.5MM")
      (footprint "easyedapro:STANDOFF_M2.5x3.5MM_RF_v1.0")
      (description "Standoff, Steel, M2.5, Hex Female-Female, 3.5 mm, 4.9 mm, WA-SMSI Series")
      (fields (field (name "Manufacturer") "WURTH ELEKTRONIK"))
      (libsource (lib "easyedapro") (part "9774035151R_RF_v1.0"))
    )
    (comp (ref "MH203")
      (value "STANDOFF_M2.5x3.5MM")
      (footprint "easyedapro:STANDOFF_M2.5x3.5MM_RF_v1.0")
      (description "Standoff, Steel, M2.5, Hex Female-Female, 3.5 mm, 4.9 mm, WA-SMSI Series")
      (fields (field (name "Manufacturer") "WURTH ELEKTRONIK"))
      (libsource (lib "easyedapro") (part "9774035151R_RF_v1.0"))
    )
    (comp (ref "MH204")
      (value "STANDOFF_M2.5x3.5MM")
      (footprint "easyedapro:STANDOFF_M2.5x3.5MM_RF_v1.0")
      (description "Standoff, Steel, M2.5, Hex Female-Female, 3.5 mm, 4.9 mm, WA-SMSI Series")
      (fields (field (name "Manufacturer") "WURTH ELEKTRONIK"))
      (libsource (lib "easyedapro") (part "9774035151R_RF_v1.0"))
    )
    (comp (ref "MH205")
      (value "~")
      (footprint "easyedapro:MH_7.5X3.2MM_RF_v1.0")
      (libsource (lib "easyedapro") (part "MH_7.5X3.2MM_RF_v1.0"))
    )
    (comp (ref "MH206")
      (value "~")
      (footprint "easyedapro:MH_7.5X3.2MM_RF_v1.0")
      (libsource (lib "easyedapro") (part "MH_7.5X3.2MM_RF_v1.0"))
    )
    (comp (ref "MH207")
      (value "~")
      (footprint "easyedapro:MH_7.5X3.2MM_RF_v1.0")
      (libsource (lib "easyedapro") (part "MH_7.5X3.2MM_RF_v1.0"))
    )
    (comp (ref "MH208")
      (value "~")
      (footprint "easyedapro:MH_7.5X3.2MM_RF_v1.0")
      (libsource (lib "easyedapro") (part "MH_7.5X3.2MM_RF_v1.0"))
    )
    (comp (ref "R201")
      (value "10kΩ")
      (footprint "easyedapro:R0402")
      (fields
        (field (name "Manufacturer Part") "0402WGF1002TCE")
        (field (name "Manufacturer") "UNI-ROYAL(厚声)")
      )
      (libsource (lib "easyedapro") (part "0402WGF1002TCE"))
    )
    (comp (ref "R202")
      (value "10kΩ")
      (footprint "easyedapro:R0402")
      (fields
        (field (name "Manufacturer Part") "0402WGF1002TCE")
        (field (name "Manufacturer") "UNI-ROYAL(厚声)")
      )
      (libsource (lib "easyedapro") (part "0402WGF1002TCE"))
    )
    (comp (ref "R203")
      (value "10kΩ")
      (footprint "easyedapro:R0402")
      (fields
        (field (name "Manufacturer Part") "0402WGF1002TCE")
        (field (name "Manufacturer") "UNI-ROYAL(厚声)")
      )
      (libsource (lib "easyedapro") (part "0402WGF1002TCE"))
    )
    (comp (ref "R204")
      (value "10kΩ")
      (footprint "easyedapro:R0402")
      (fields
        (field (name "Manufacturer Part") "0402WGF1002TCE")
        (field (name "Manufacturer") "UNI-ROYAL(厚声)")
      )
      (libsource (lib "easyedapro") (part "0402WGF1002TCE"))
    )
    (comp (ref "R205")
      (value "10kΩ")
      (footprint "easyedapro:R0402")
      (fields
        (field (name "Manufacturer Part") "0402WGF1002TCE")
        (field (name "Manufacturer") "UNI-ROYAL(厚声)")
      )
      (libsource (lib "easyedapro") (part "0402WGF1002TCE"))
    )
    (comp (ref "R206")
      (value "10kΩ")
      (footprint "easyedapro:R0402")
      (fields
        (field (name "Manufacturer Part") "0402WGF1002TCE")
        (field (name "Manufacturer") "UNI-ROYAL(厚声)")
      )
      (libsource (lib "easyedapro") (part "0402WGF1002TCE"))
    )
    (comp (ref "R207")
      (value "10kΩ")
      (footprint "easyedapro:R0402")
      (fields
        (field (name "Manufacturer Part") "0402WGF1002TCE")
        (field (name "Manufacturer") "UNI-ROYAL(厚声)")
      )
      (libsource (lib "easyedapro") (part "0402WGF1002TCE"))
    )
    (comp (ref "R208")
      (value "10kΩ")
      (footprint "easyedapro:R0402")
      (fields
        (field (name "Manufacturer Part") "0402WGF1002TCE")
        (field (name "Manufacturer") "UNI-ROYAL(厚声)")
      )
      (libsource (lib "easyedapro") (part "0402WGF1002TCE"))
    )
    (comp (ref "R209")
      (value "10kΩ")
      (footprint "easyedapro:R0402")
      (fields
        (field (name "Manufacturer Part") "0402WGF1002TCE")
        (field (name "Manufacturer") "UNI-ROYAL(厚声)")
      )
      (libsource (lib "easyedapro") (part "0402WGF1002TCE"))
    )
    (comp (ref "R210")
      (value "10kΩ")
      (footprint "easyedapro:R0402")
      (fields
        (field (name "Manufacturer Part") "0402WGF1002TCE")
        (field (name "Manufacturer") "UNI-ROYAL(厚声)")
      )
      (libsource (lib "easyedapro") (part "0402WGF1002TCE"))
    )
    (comp (ref "R211")
      (value "10kΩ")
      (footprint "easyedapro:R0402")
      (fields
        (field (name "Manufacturer Part") "0402WGF1002TCE")
        (field (name "Manufacturer") "UNI-ROYAL(厚声)")
      )
      (libsource (lib "easyedapro") (part "0402WGF1002TCE"))
    )
    (comp (ref "R212")
      (value "10kΩ")
      (footprint "easyedapro:R0402")
      (fields
        (field (name "Manufacturer Part") "0402WGF1002TCE")
        (field (name "Manufacturer") "UNI-ROYAL(厚声)")
      )
      (libsource (lib "easyedapro") (part "0402WGF1002TCE"))
    )
    (comp (ref "SW201")
      (value "CPG151101S21")
      (footprint "easyedapro:KEY-TH_CPG1511F01S0X_1")
      (fields (field (name "Manufacturer") "Kailh(凯华)"))
      (libsource (lib "easyedapro") (part "CPG151101S21 RF v1.0"))
    )
    (comp (ref "SW202")
      (value "CPG151101S21")
      (footprint "easyedapro:KEY-TH_CPG1511F01S0X_1")
      (fields (field (name "Manufacturer") "Kailh(凯华)"))
      (libsource (lib "easyedapro") (part "CPG151101S21 RF v1.0"))
    )
    (comp (ref "SW203")
      (value "CPG151101S21")
      (footprint "easyedapro:KEY-TH_CPG1511F01S0X_1")
      (fields (field (name "Manufacturer") "Kailh(凯华)"))
      (libsource (lib "easyedapro") (part "CPG151101S21 RF v1.0"))
    )
    (comp (ref "SW204")
      (value "CPG151101S21")
      (footprint "easyedapro:KEY-TH_CPG1511F01S0X_1")
      (fields (field (name "Manufacturer") "Kailh(凯华)"))
      (libsource (lib "easyedapro") (part "CPG151101S21 RF v1.0"))
    )
    (comp (ref "SW205")
      (value "CPG151101S21")
      (footprint "easyedapro:KEY-TH_CPG1511F01S0X_1")
      (fields (field (name "Manufacturer") "Kailh(凯华)"))
      (libsource (lib "easyedapro") (part "CPG151101S21 RF v1.0"))
    )
    (comp (ref "SW206")
      (value "CPG151101S21")
      (footprint "easyedapro:KEY-TH_CPG1511F01S0X_1")
      (fields (field (name "Manufacturer") "Kailh(凯华)"))
      (libsource (lib "easyedapro") (part "CPG151101S21 RF v1.0"))
    )
    (comp (ref "SW207")
      (value "CPG151101S21")
      (footprint "easyedapro:KEY-TH_CPG1511F01S0X_1")
      (fields (field (name "Manufacturer") "Kailh(凯华)"))
      (libsource (lib "easyedapro") (part "CPG151101S21 RF v1.0"))
    )
    (comp (ref "SW208")
      (value "CPG151101S21")
      (footprint "easyedapro:KEY-TH_CPG1511F01S0X_1")
      (fields (field (name "Manufacturer") "Kailh(凯华)"))
      (libsource (lib "easyedapro") (part "CPG151101S21 RF v1.0"))
    )
    (comp (ref "SW209")
      (value "CPG151101S21")
      (footprint "easyedapro:KEY-TH_CPG1511F01S0X_1")
      (fields (field (name "Manufacturer") "Kailh(凯华)"))
      (libsource (lib "easyedapro") (part "CPG151101S21 RF v1.0"))
    )
  )
  (nets
    (net (code "1") (name "+1V1") (class "Default")
      (node (ref "C107") (pin "2") (pinfunction "2_2") (pintype "unspecified"))
      (node (ref "C108") (pin "2") (pinfunction "2_2") (pintype "unspecified"))
      (node (ref "C109") (pin "2") (pinfunction "2_2") (pintype "unspecified"))
      (node (ref "U101") (pin "23") (pinfunction "DVDD_23") (pintype "bidirectional"))
      (node (ref "U101") (pin "45") (pinfunction "VREG_VOUT_45") (pintype "bidirectional"))
      (node (ref "U101") (pin "50") (pinfunction "DVDD_50") (pintype "bidirectional"))
    )
    (net (code "2") (name "+3V3") (class "Default")
      (node (ref "C101") (pin "2") (pinfunction "2_2") (pintype "unspecified"))
      (node (ref "C102") (pin "2") (pinfunction "2_2") (pintype "unspecified"))
      (node (ref "C103") (pin "2") (pinfunction "2_2") (pintype "unspecified"))
      (node (ref "C104") (pin "2") (pinfunction "2_2") (pintype "unspecified"))
      (node (ref "C106") (pin "2") (pinfunction "2_2") (pintype "unspecified"))
      (node (ref "C112") (pin "2") (pinfunction "2_2") (pintype "unspecified"))
      (node (ref "C113") (pin "2") (pinfunction "2_2") (pintype "unspecified"))
      (node (ref "C114") (pin "2") (pinfunction "2_2") (pintype "unspecified"))
      (node (ref "C115") (pin "2") (pinfunction "2_2") (pintype "unspecified"))
      (node (ref "C116") (pin "2") (pinfunction "2_2") (pintype "unspecified"))
      (node (ref "C126") (pin "2") (pinfunction "2_2") (pintype "unspecified"))
      (node (ref "C201") (pin "2") (pinfunction "2_2") (pintype "unspecified"))
      (node (ref "C202") (pin "2") (pinfunction "2_2") (pintype "unspecified"))
      (node (ref "C207") (pin "2") (pinfunction "2_2") (pintype "unspecified"))
      (node (ref "LED101") (pin "1") (pinfunction "+_1") (pintype "unspecified"))
      (node (ref "R101") (pin "1") (pinfunction "1_1") (pintype "input"))
      (node (ref "R104") (pin "2") (pinfunction "2_2") (pintype "input"))
      (node (ref "R122") (pin "2") (pinfunction "2_2") (pintype "input"))
      (node (ref "R123") (pin "2") (pinfunction "2_2") (pintype "input"))
      (node (ref "R201") (pin "2") (pinfunction "2_2") (pintype "input"))
      (node (ref "R202") (pin "2") (pinfunction "2_2") (pintype "input"))
      (node (ref "R203") (pin "2") (pinfunction "2_2") (pintype "input"))
      (node (ref "R204") (pin "2") (pinfunction "2_2") (pintype "input"))
      (node (ref "R209") (pin "2") (pinfunction "2_2") (pintype "input"))
      (node (ref "R210") (pin "2") (pinfunction "2_2") (pintype "input"))
      (node (ref "U101") (pin "1") (pinfunction "IOVDD_1") (pintype "bidirectional"))
      (node (ref "U101") (pin "10") (pinfunction "IOVDD_10") (pintype "bidirectional"))
      (node (ref "U101") (pin "22") (pinfunction "IOVDD_22") (pintype "bidirectional"))
      (node (ref "U101") (pin "33") (pinfunction "IOVDD_33") (pintype "bidirectional"))
      (node (ref "U101") (pin "42") (pinfunction "IOVDD_42") (pintype "bidirectional"))
      (node (ref "U101") (pin "44") (pinfunction "VREG_IN_44") (pintype "bidirectional"))
      (node (ref "U101") (pin "48") (pinfunction "USB_VDD_48") (pintype "bidirectional"))
      (node (ref "U101") (pin "49") (pinfunction "IOVDD_49") (pintype "bidirectional"))
      (node (ref "U102") (pin "3") (pinfunction "OUT_3") (pintype "unspecified"))
      (node (ref "U104") (pin "8") (pinfunction "VCC_8") (pintype "unspecified"))
    )
    (net (code "3") (name "+3V3_A") (class "Default")
      (node (ref "C105") (pin "2") (pinfunction "2_2") (pintype "unspecified"))
      (node (ref "R101") (pin "2") (pinfunction "2_2") (pintype "input"))
      (node (ref "U101") (pin "43") (pinfunction "ADC_AVDD_43") (pintype "bidirectional"))
    )
    (net (code "4") (name "+5V_LEDS") (class "Default")
      (node (ref "C110") (pin "2") (pinfunction "2_2") (pintype "unspecified"))
      (node (ref "C210") (pin "2") (pinfunction "2_2") (pintype "unspecified"))
      (node (ref "C211") (pin "2") (pinfunction "2_2") (pintype "unspecified"))
      (node (ref "C212") (pin "2") (pinfunction "2_2") (pintype "unspecified"))
      (node (ref "C213") (pin "2") (pinfunction "2_2") (pintype "unspecified"))
      (node (ref "C214") (pin "2") (pinfunction "2_2") (pintype "unspecified"))
      (node (ref "C215") (pin "2") (pinfunction "2_2") (pintype "unspecified"))
      (node (ref "C216") (pin "2") (pinfunction "2_2") (pintype "unspecified"))
      (node (ref "C217") (pin "2") (pinfunction "2_2") (pintype "unspecified"))
      (node (ref "C218") (pin "2") (pinfunction "2_2") (pintype "unspecified"))
      (node (ref "LED201") (pin "1") (pinfunction "VDD_1") (pintype "unspecified"))
      (node (ref "LED202") (pin "1") (pinfunction "VDD_1") (pintype "unspecified"))
      (node (ref "LED203") (pin "1") (pinfunction "VDD_1") (pintype "unspecified"))
      (node (ref "LED204") (pin "1") (pinfunction "VDD_1") (pintype "unspecified"))
      (node (ref "LED205") (pin "1") (pinfunction "VDD_1") (pintype "unspecified"))
      (node (ref "LED206") (pin "1") (pinfunction "VDD_1") (pintype "unspecified"))
      (node (ref "LED207") (pin "1") (pinfunction "VDD_1") (pintype "unspecified"))
      (node (ref "LED208") (pin "1") (pinfunction "VDD_1") (pintype "unspecified"))
      (node (ref "LED209") (pin "1") (pinfunction "VDD_1") (pintype "unspecified"))
      (node (ref "R102") (pin "2") (pinfunction "2_2") (pintype "input"))
    )
    (net (code "5") (name "+5V_USB") (class "Default")
      (node (ref "C111") (pin "2") (pinfunction "2_2") (pintype "unspecified"))
      (node (ref "C118") (pin "2") (pinfunction "2_2") (pintype "unspecified"))
      (node (ref "C119") (pin "2") (pinfunction "2_2") (pintype "unspecified"))
      (node (ref "C125") (pin "2") (pinfunction "2_2") (pintype "unspecified"))
      (node (ref "D101") (pin "2") (pinfunction "2_2") (pintype "input"))
      (node (ref "D102") (pin "2") (pinfunction "2_2") (pintype "input"))
      (node (ref "J101") (pin "11") (pinfunction "VBUS_11") (pintype "unspecified"))
      (node (ref "J101") (pin "2") (pinfunction "VBUS_2") (pintype "unspecified"))
      (node (ref "R102") (pin "1") (pinfunction "1_1") (pintype "input"))
      (node (ref "U102") (pin "1") (pinfunction "IN_1") (pintype "unspecified"))
      (node (ref "U103") (pin "5") (pinfunction "VCC_5") (pintype "unspecified"))
    )
    (net (code "6") (name "COL0") (class "Default")
      (node (ref "ENC201") (pin "1") (pinfunction "1_1") (pintype "input"))
      (node (ref "J201") (pin "1") (pinfunction "1_1") (pintype "input"))
      (node (ref "J204") (pin "1") (pinfunction "1_1") (pintype "input"))
      (node (ref "J207") (pin "1") (pinfunction "1_1") (pintype "input"))
      (node (ref "R108") (pin "2") (pinfunction "2_2") (pintype "input"))
    )
    (net (code "7") (name "COL0_R") (class "Default")
      (node (ref "R108") (pin "1") (pinfunction "1_1") (pintype "input"))
      (node (ref "U101") (pin "2") (pinfunction "GPIO0_2") (pintype "bidirectional"))
    )
    (net (code "8") (name "COL1") (class "Default")
      (node (ref "ENC202") (pin "1") (pinfunction "1_1") (pintype "input"))
      (node (ref "J202") (pin "1") (pinfunction "1_1") (pintype "input"))
      (node (ref "J205") (pin "1") (pinfunction "1_1") (pintype "input"))
      (node (ref "J208") (pin "1") (pinfunction "1_1") (pintype "input"))
      (node (ref "R110") (pin "2") (pinfunction "2_2") (pintype "input"))
    )
    (net (code "9") (name "COL1_R") (class "Default")
      (node (ref "R110") (pin "1") (pinfunction "1_1") (pintype "input"))
      (node (ref "U101") (pin "3") (pinfunction "GPIO1_3") (pintype "bidirectional"))
    )
    (net (code "10") (name "COL2") (class "Default")
      (node (ref "ENC203") (pin "1") (pinfunction "1_1") (pintype "input"))
      (node (ref "J203") (pin "1") (pinfunction "1_1") (pintype "input"))
      (node (ref "J206") (pin "1") (pinfunction "1_1") (pintype "input"))
      (node (ref "J209") (pin "1") (pinfunction "1_1") (pintype "input"))
      (node (ref "R112") (pin "2") (pinfunction "2_2") (pintype "input"))
    )
    (net (code "11") (name "COL2_R") (class "Default")
      (node (ref "R112") (pin "1") (pinfunction "1_1") (pintype "input"))
      (node (ref "U101") (pin "4") (pinfunction "GPIO2_4") (pintype "bidirectional"))
    )
    (net (code "12") (name "CON_USB_N") (class "Default")
      (node (ref "D103") (pin "2") (pinfunction "2_2") (pintype "input"))
      (node (ref "J101") (pin "5") (pinfunction "DN2_5") (pintype "unspecified"))
      (node (ref "J101") (pin "7") (pinfunction "DN1_7") (pintype "unspecified"))
      (node (ref "R109") (pin "1") (pinfunction "1_1") (pintype "input"))
    )
    (net (code "13") (name "CON_USB_P") (class "Default")
      (node (ref "D104") (pin "2") (pinfunction "2_2") (pintype "input"))
      (node (ref "J101") (pin "6") (pinfunction "DP1_6") (pintype "unspecified"))
      (node (ref "J101") (pin "8") (pinfunction "DP2_8") (pintype "unspecified"))
      (node (ref "R111") (pin "1") (pinfunction "1_1") (pintype "input"))
    )
    (net (code "14") (name "ENC1_A") (class "Default")
      (node (ref "C203") (pin "2") (pinfunction "2_2") (pintype "input"))
      (node (ref "R205") (pin "1") (pinfunction "1_1") (pintype "input"))
      (node (ref "U101") (pin "18") (pinfunction "GPIO15_18") (pintype "bidirectional"))
    )
    (net (code "15") (name "ENC1_B") (class "Default")
      (node (ref "C204") (pin "2") (pinfunction "2_2") (pintype "input"))
      (node (ref "R207") (pin "1") (pinfunction "1_1") (pintype "input"))
      (node (ref "U101") (pin "27") (pinfunction "GPIO16_27") (pintype "bidirectional"))
    )
    (net (code "16") (name "ENC1_SW") (class "Default")
      (node (ref "D210") (pin "2") (pinfunction "A_2") (pintype "input"))
      (node (ref "ENC201") (pin "2") (pinfunction "2_2") (pintype "input"))
    )
    (net (code "17") (name "ENC2_A") (class "Default")
      (node (ref "C205") (pin "2") (pinfunction "2_2") (pintype "input"))
      (node (ref "R206") (pin "1") (pinfunction "1_1") (pintype "input"))
      (node (ref "U101") (pin "28") (pinfunction "GPIO17_28") (pintype "bidirectional"))
    )
    (net (code "18") (name "ENC2_B") (class "Default")
      (node (ref "C206") (pin "2") (pinfunction "2_2") (pintype "input"))
      (node (ref "R208") (pin "1") (pinfunction "1_1") (pintype "input"))
      (node (ref "U101") (pin "29") (pinfunction "GPIO18_29") (pintype "bidirectional"))
    )
    (net (code "19") (name "ENC2_SW") (class "Default")
      (node (ref "D211") (pin "2") (pinfunction "A_2") (pintype "input"))
      (node (ref "ENC202") (pin "2") (pinfunction "2_2") (pintype "input"))
    )
    (net (code "20") (name "ENC3_A") (class "Default")
      (node (ref "C208") (pin "2") (pinfunction "2_2") (pintype "input"))
      (node (ref "R211") (pin "1") (pinfunction "1_1") (pintype "input"))
      (node (ref "U101") (pin "30") (pinfunction "GPIO19_30") (pintype "bidirectional"))
    )
    (net (code "21") (name "ENC3_B") (class "Default")
      (node (ref "C209") (pin "2") (pinfunction "2_2") (pintype "input"))
      (node (ref "R212") (pin "1") (pinfunction "1_1") (pintype "input"))
      (node (ref "U101") (pin "31") (pinfunction "GPIO20_31") (pintype "bidirectional"))
    )
    (net (code "22") (name "ENC3_SW") (class "Default")
      (node (ref "D212") (pin "2") (pinfunction "A_2") (pintype "input"))
      (node (ref "ENC203") (pin "2") (pinfunction "2_2") (pintype "input"))
    )
    (net (code "23") (name "GND") (class "Default")
      (node (ref "C101") (pin "1") (pinfunction "1_1") (pintype "unspecified"))
      (node (ref "C102") (pin "1") (pinfunction "1_1") (pintype "unspecified"))
      (node (ref "C103") (pin "1") (pinfunction "1_1") (pintype "unspecified"))
      (node (ref "C104") (pin "1") (pinfunction "1_1") (pintype "unspecified"))
      (node (ref "C105") (pin "1") (pinfunction "1_1") (pintype "unspecified"))
      (node (ref "C106") (pin "1") (pinfunction "1_1") (pintype "unspecified"))
      (node (ref "C107") (pin "1") (pinfunction "1_1") (pintype "unspecified"))
      (node (ref "C108") (pin "1") (pinfunction "1_1") (pintype "unspecified"))
      (node (ref "C109") (pin "1") (pinfunction "1_1") (pintype "unspecified"))
      (node (ref "C110") (pin "1") (pinfunction "1_1") (pintype "unspecified"))
      (node (ref "C111") (pin "1") (pinfunction "1_1") (pintype "unspecified"))
      (node (ref "C112") (pin "1") (pinfunction "1_1") (pintype "unspecified"))
      (node (ref "C113") (pin "1") (pinfunction "1_1") (pintype "unspecified"))
      (node (ref "C114") (pin "1") (pinfunction "1_1") (pintype "unspecified"))
      (node (ref "C115") (pin "1") (pinfunction "1_1") (pintype "unspecified"))
      (node (ref "C116") (pin "1") (pinfunction "1_1") (pintype "unspecified"))
      (node (ref "C117") (pin "1") (pinfunction "1_1") (pintype "unspecified"))
      (node (ref "C118") (pin "1") (pinfunction "1_1") (pintype "unspecified"))
      (node (ref "C119") (pin "1") (pinfunction "1_1") (pintype "unspecified"))
      (node (ref "C120") (pin "1") (pinfunction "1_1") (pintype "unspecified"))
      (node (ref "C121") (pin "1") (pinfunction "1_1") (pintype "unspecified"))
      (node (ref "C122") (pin "1") (pinfunction "1_1") (pintype "unspecified"))
      (node (ref "C123") (pin "2") (pinfunction "2_2") (pintype "unspecified"))
      (node (ref "C124") (pin "2") (pinfunction "2_2") (pintype "unspecified"))
      (node (ref "C125") (pin "1") (pinfunction "1_1") (pintype "unspecified"))
      (node (ref "C126") (pin "1") (pinfunction "1_1") (pintype "unspecified"))
      (node (ref "C127") (pin "1") (pinfunction "1_1") (pintype "unspecified"))
      (node (ref "C201") (pin "1") (pinfunction "1_1") (pintype "unspecified"))
      (node (ref "C202") (pin "1") (pinfunction "1_1") (pintype "unspecified"))
      (node (ref "C203") (pin "1") (pinfunction "1_1") (pintype "input"))
      (node (ref "C204") (pin "1") (pinfunction "1_1") (pintype "input"))
      (node (ref "C205") (pin "1") (pinfunction "1_1") (pintype "input"))
      (node (ref "C206") (pin "1") (pinfunction "1_1") (pintype "input"))
      (node (ref "C207") (pin "1") (pinfunction "1_1") (pintype "unspecified"))
      (node (ref "C208") (pin "1") (pinfunction "1_1") (pintype "input"))
      (node (ref "C209") (pin "1") (pinfunction "1_1") (pintype "input"))
      (node (ref "C210") (pin "1") (pinfunction "1_1") (pintype "unspecified"))
      (node (ref "C211") (pin "1") (pinfunction "1_1") (pintype "unspecified"))
      (node (ref "C212") (pin "1") (pinfunction "1_1") (pintype "unspecified"))
      (node (ref "C213") (pin "1") (pinfunction "1_1") (pintype "unspecified"))
      (node (ref "C214") (pin "1") (pinfunction "1_1") (pintype "unspecified"))
      (node (ref "C215") (pin "1") (pinfunction "1_1") (pintype "unspecified"))
      (node (ref "C216") (pin "1") (pinfunction "1_1") (pintype "unspecified"))
      (node (ref "C217") (pin "1") (pinfunction "1_1") (pintype "unspecified"))
      (node (ref "C218") (pin "1") (pinfunction "1_1") (pintype "unspecified"))
      (node (ref "D101") (pin "1") (pinfunction "1_1") (pintype "input"))
      (node (ref "D102") (pin "1") (pinfunction "1_1") (pintype "input"))
      (node (ref "D103") (pin "1") (pinfunction "1_1") (pintype "input"))
      (node (ref "D104") (pin "1") (pinfunction "1_1") (pintype "input"))
      (node (ref "ENC201") (pin "3") (pinfunction "3_3") (pintype "input"))
      (node (ref "ENC201") (pin "4") (pinfunction "4_4") (pintype "input"))
      (node (ref "ENC201") (pin "C") (pinfunction "C_C") (pintype "input"))
      (node (ref "ENC202") (pin "3") (pinfunction "3_3") (pintype "input"))
      (node (ref "ENC202") (pin "4") (pinfunction "4_4") (pintype "input"))
      (node (ref "ENC202") (pin "C") (pinfunction "C_C") (pintype "input"))
      (node (ref "ENC203") (pin "3") (pinfunction "3_3") (pintype "input"))
      (node (ref "ENC203") (pin "4") (pinfunction "4_4") (pintype "input"))
      (node (ref "ENC203") (pin "C") (pinfunction "C_C") (pintype "input"))
      (node (ref "J101") (pin "1") (pinfunction "GND_1") (pintype "unspecified"))
      (node (ref "J101") (pin "12") (pinfunction "GND_12") (pintype "unspecified"))
      (node (ref "J101") (pin "13") (pinfunction "SHELL_13") (pintype "unspecified"))
      (node (ref "J101") (pin "14") (pinfunction "SHELL_14") (pintype "unspecified"))
      (node (ref "J102") (pin "2") (pinfunction "2_2") (pintype "input"))
      (node (ref "LED102") (pin "2") (pinfunction "K_2") (pintype "unspecified"))
      (node (ref "LED103") (pin "2") (pinfunction "-_2") (pintype "unspecified"))
      (node (ref "LED201") (pin "3") (pinfunction "GND_3") (pintype "unspecified"))
      (node (ref "LED202") (pin "3") (pinfunction "GND_3") (pintype "unspecified"))
      (node (ref "LED203") (pin "3") (pinfunction "GND_3") (pintype "unspecified"))
      (node (ref "LED204") (pin "3") (pinfunction "GND_3") (pintype "unspecified"))
      (node (ref "LED205") (pin "3") (pinfunction "GND_3") (pintype "unspecified"))
      (node (ref "LED206") (pin "3") (pinfunction "GND_3") (pintype "unspecified"))
      (node (ref "LED207") (pin "3") (pinfunction "GND_3") (pintype "unspecified"))
      (node (ref "LED208") (pin "3") (pinfunction "GND_3") (pintype "unspecified"))
      (node (ref "LED209") (pin "3") (pinfunction "GND_3") (pintype "unspecified"))
      (node (ref "MH201") (pin "1") (pinfunction "1_1") (pintype "input"))
      (node (ref "MH202") (pin "1") (pinfunction "1_1") (pintype "input"))
      (node (ref "MH203") (pin "1") (pinfunction "1_1") (pintype "input"))
      (node (ref "MH204") (pin "1") (pinfunction "1_1") (pintype "input"))
      (node (ref "MH205") (pin "1") (pinfunction "1_1") (pintype "input"))
      (node (ref "MH206") (pin "1") (pinfunction "1_1") (pintype "input"))
      (node (ref "MH207") (pin "1") (pinfunction "1_1") (pintype "input"))
      (node (ref "MH208") (pin "1") (pinfunction "1_1") (pintype "input"))
      (node (ref "R118") (pin "1") (pinfunction "1_1") (pintype "input"))
      (node (ref "R119") (pin "1") (pinfunction "1_1") (pintype "input"))
      (node (ref "SW101") (pin "1") (pinfunction "A_1") (pintype "input"))
      (node (ref "SW101") (pin "2") (pinfunction "B_2") (pintype "input"))
      (node (ref "SW102") (pin "1") (pinfunction "A_1") (pintype "input"))
      (node (ref "SW102") (pin "2") (pinfunction "B_2") (pintype "input"))
      (node (ref "U101") (pin "19") (pinfunction "TESTEN_19") (pintype "unspecified"))
      (node (ref "U101") (pin "57") (pinfunction "GND_57") (pintype "bidirectional"))
      (node (ref "U102") (pin "2") (pinfunction "GND_2") (pintype "unspecified"))
      (node (ref "U102") (pin "4") (pinfunction "GND_4") (pintype "unspecified"))
      (node (ref "U103") (pin "3") (pinfunction "GND_3") (pintype "unspecified"))
      (node (ref "U104") (pin "4") (pinfunction "GND_4") (pintype "unspecified"))
      (node (ref "Y101") (pin "2") (pinfunction "GND_2") (pintype "input"))
      (node (ref "Y101") (pin "4") (pinfunction "GND_4") (pintype "input"))
    )
    (net (code "24") (name "LED0_BUF") (class "Default")
      (node (ref "R117") (pin "2") (pinfunction "2_2") (pintype "input"))
      (node (ref "U103") (pin "1") (pinfunction "NC_1") (pintype "unspecified"))
      (node (ref "U103") (pin "2") (pinfunction "A_2") (pintype "unspecified"))
    )
    (net (code "25") (name "LED0_DIN") (class "Default")
      (node (ref "LED201") (pin "4") (pinfunction "DIN_4") (pintype "unspecified"))
      (node (ref "U103") (pin "4") (pinfunction "Y_4") (pintype "unspecified"))
    )
    (net (code "26") (name "LED0_RES") (class "Default")
      (node (ref "R117") (pin "1") (pinfunction "1_1") (pintype "input"))
      (node (ref "U101") (pin "36") (pinfunction "GPIO24_36") (pintype "bidirectional"))
    )
    (net (code "27") (name "LED1_DIN") (class "Default")
      (node (ref "LED201") (pin "2") (pinfunction "DOUT_2") (pintype "unspecified"))
      (node (ref "LED202") (pin "4") (pinfunction "DIN_4") (pintype "unspecified"))
    )
    (net (code "28") (name "LED2_DIN") (class "Default")
      (node (ref "LED202") (pin "2") (pinfunction "DOUT_2") (pintype "unspecified"))
      (node (ref "LED203") (pin "4") (pinfunction "DIN_4") (pintype "unspecified"))
    )
    (net (code "29") (name "LED3_DIN") (class "Default")
      (node (ref "LED203") (pin "2") (pinfunction "DOUT_2") (pintype "unspecified"))
      (node (ref "LED204") (pin "4") (pinfunction "DIN_4") (pintype "unspecified"))
    )
    (net (code "30") (name "LED4_DIN") (class "Default")
      (node (ref "LED204") (pin "2") (pinfunction "DOUT_2") (pintype "unspecified"))
      (node (ref "LED205") (pin "4") (pinfunction "DIN_4") (pintype "unspecified"))
    )
    (net (code "31") (name "LED5_DIN") (class "Default")
      (node (ref "LED205") (pin "2") (pinfunction "DOUT_2") (pintype "unspecified"))
      (node (ref "LED206") (pin "4") (pinfunction "DIN_4") (pintype "unspecified"))
    )
    (net (code "32") (name "LED6_DIN") (class "Default")
      (node (ref "LED206") (pin "2") (pinfunction "DOUT_2") (pintype "unspecified"))
      (node (ref "LED207") (pin "4") (pinfunction "DIN_4") (pintype "unspecified"))
    )
    (net (code "33") (name "LED7_DIN") (class "Default")
      (node (ref "LED207") (pin "2") (pinfunction "DOUT_2") (pintype "unspecified"))
      (node (ref "LED208") (pin "4") (pinfunction "DIN_4") (pintype "unspecified"))
    )
    (net (code "34") (name "LED8_DIN") (class "Default")
      (node (ref "LED208") (pin "2") (pinfunction "DOUT_2") (pintype "unspecified"))
      (node (ref "LED209") (pin "4") (pinfunction "DIN_4") (pintype "unspecified"))
    )
    (net (code "35") (name "Net-(D201-A)") (class "Default")
      (node (ref "D201") (pin "2") (pinfunction "A_2") (pintype "input"))
      (node (ref "J201") (pin "2") (pinfunction "2_2") (pintype "input"))
    )
    (net (code "36") (name "Net-(D202-A)") (class "Default")
      (node (ref "D202") (pin "2") (pinfunction "A_2") (pintype "input"))
      (node (ref "J202") (pin "2") (pinfunction "2_2") (pintype "input"))
    )
    (net (code "37") (name "Net-(D203-A)") (class "Default")
      (node (ref "D203") (pin "2") (pinfunction "A_2") (pintype "input"))
      (node (ref "J203") (pin "2") (pinfunction "2_2") (pintype "input"))
    )
    (net (code "38") (name "Net-(D204-A)") (class "Default")
      (node (ref "D204") (pin "2") (pinfunction "A_2") (pintype "input"))
      (node (ref "J204") (pin "2") (pinfunction "2_2") (pintype "input"))
    )
    (net (code "39") (name "Net-(D205-A)") (class "Default")
      (node (ref "D205") (pin "2") (pinfunction "A_2") (pintype "input"))
      (node (ref "J205") (pin "2") (pinfunction "2_2") (pintype "input"))
    )
    (net (code "40") (name "Net-(D206-A)") (class "Default")
      (node (ref "D206") (pin "2") (pinfunction "A_2") (pintype "input"))
      (node (ref "J206") (pin "2") (pinfunction "2_2") (pintype "input"))
    )
    (net (code "41") (name "Net-(D207-A)") (class "Default")
      (node (ref "D207") (pin "2") (pinfunction "A_2") (pintype "input"))
      (node (ref "J207") (pin "2") (pinfunction "2_2") (pintype "input"))
    )
    (net (code "42") (name "Net-(D208-A)") (class "Default")
      (node (ref "D208") (pin "2") (pinfunction "A_2") (pintype "input"))
      (node (ref "J208") (pin "2") (pinfunction "2_2") (pintype "input"))
    )
    (net (code "43") (name "Net-(D209-A)") (class "Default")
      (node (ref "D209") (pin "2") (pinfunction "A_2") (pintype "input"))
      (node (ref "J209") (pin "2") (pinfunction "2_2") (pintype "input"))
    )
    (net (code "44") (name "Net-(ENC201-PadA)") (class "Default")
      (node (ref "ENC201") (pin "A") (pinfunction "A_A") (pintype "input"))
      (node (ref "R201") (pin "1") (pinfunction "1_1") (pintype "input"))
      (node (ref "R205") (pin "2") (pinfunction "2_2") (pintype "input"))
    )
    (net (code "45") (name "Net-(ENC201-PadB)") (class "Default")
      (node (ref "ENC201") (pin "B") (pinfunction "B_B") (pintype "input"))
      (node (ref "R202") (pin "1") (pinfunction "1_1") (pintype "input"))
      (node (ref "R207") (pin "2") (pinfunction "2_2") (pintype "input"))
    )
    (net (code "46") (name "Net-(ENC202-PadA)") (class "Default")
      (node (ref "ENC202") (pin "A") (pinfunction "A_A") (pintype "input"))
      (node (ref "R203") (pin "1") (pinfunction "1_1") (pintype "input"))
      (node (ref "R206") (pin "2") (pinfunction "2_2") (pintype "input"))
    )
    (net (code "47") (name "Net-(ENC202-PadB)") (class "Default")
      (node (ref "ENC202") (pin "B") (pinfunction "B_B") (pintype "input"))
      (node (ref "R204") (pin "1") (pinfunction "1_1") (pintype "input"))
      (node (ref "R208") (pin "2") (pinfunction "2_2") (pintype "input"))
    )
    (net (code "48") (name "Net-(ENC203-PadA)") (class "Default")
      (node (ref "ENC203") (pin "A") (pinfunction "A_A") (pintype "input"))
      (node (ref "R209") (pin "1") (pinfunction "1_1") (pintype "input"))
      (node (ref "R211") (pin "2") (pinfunction "2_2") (pintype "input"))
    )
    (net (code "49") (name "Net-(ENC203-PadB)") (class "Default")
      (node (ref "ENC203") (pin "B") (pinfunction "B_B") (pintype "input"))
      (node (ref "R210") (pin "1") (pinfunction "1_1") (pintype "input"))
      (node (ref "R212") (pin "2") (pinfunction "2_2") (pintype "input"))
    )
    (net (code "50") (name "Net-(J101-CC1)") (class "Default")
      (node (ref "J101") (pin "4") (pinfunction "CC1_4") (pintype "unspecified"))
      (node (ref "R119") (pin "2") (pinfunction "2_2") (pintype "input"))
    )
    (net (code "51") (name "Net-(J101-CC2)") (class "Default")
      (node (ref "J101") (pin "10") (pinfunction "CC2_10") (pintype "unspecified"))
      (node (ref "R118") (pin "2") (pinfunction "2_2") (pintype "input"))
    )
    (net (code "52") (name "Net-(LED101---Pad2)") (class "Default")
      (node (ref "LED101") (pin "2") (pinfunction "-_2") (pintype "unspecified"))
      (node (ref "R105") (pin "1") (pinfunction "1_1") (pintype "input"))
    )
    (net (code "53") (name "Net-(LED101---Pad3)") (class "Default")
      (node (ref "LED101") (pin "3") (pinfunction "-_3") (pintype "unspecified"))
      (node (ref "R106") (pin "1") (pinfunction "1_1") (pintype "input"))
    )
    (net (code "54") (name "Net-(LED101---Pad4)") (class "Default")
      (node (ref "LED101") (pin "4") (pinfunction "-_4") (pintype "unspecified"))
      (node (ref "R107") (pin "1") (pinfunction "1_1") (pintype "input"))
    )
    (net (code "55") (name "Net-(LED102-A)") (class "Default")
      (node (ref "LED102") (pin "1") (pinfunction "A_1") (pintype "unspecified"))
      (node (ref "R104") (pin "1") (pinfunction "1_1") (pintype "input"))
    )
    (net (code "56") (name "Net-(LED103-+)") (class "Default")
      (node (ref "LED103") (pin "1") (pinfunction "+_1") (pintype "unspecified"))
      (node (ref "R103") (pin "1") (pinfunction "1_1") (pintype "input"))
    )
    (net (code "57") (name "Net-(SW101-C)") (class "Default")
      (node (ref "R122") (pin "1") (pinfunction "1_1") (pintype "input"))
      (node (ref "R124") (pin "1") (pinfunction "1_1") (pintype "input"))
      (node (ref "SW101") (pin "3") (pinfunction "C_3") (pintype "input"))
      (node (ref "SW101") (pin "4") (pinfunction "D_4") (pintype "input"))
    )
    (net (code "58") (name "Net-(SW102-C)") (class "Default")
      (node (ref "R123") (pin "1") (pinfunction "1_1") (pintype "input"))
      (node (ref "R125") (pin "1") (pinfunction "1_1") (pintype "input"))
      (node (ref "SW102") (pin "3") (pinfunction "C_3") (pintype "input"))
      (node (ref "SW102") (pin "4") (pinfunction "D_4") (pintype "input"))
    )
    (net (code "59") (name "QSPI_SCLK") (class "Default")
      (node (ref "U101") (pin "52") (pinfunction "QSPI_SCLK_52") (pintype "output"))
      (node (ref "U104") (pin "6") (pinfunction "CLK_6") (pintype "unspecified"))
    )
    (net (code "60") (name "QSPI_SD0") (class "Default")
      (node (ref "U101") (pin "53") (pinfunction "QSPI_SD0_53") (pintype "bidirectional"))
      (node (ref "U104") (pin "5") (pinfunction "DI_5") (pintype "unspecified"))
    )
    (net (code "61") (name "QSPI_SD1") (class "Default")
      (node (ref "U101") (pin "55") (pinfunction "QSPI_SD1_55") (pintype "bidirectional"))
      (node (ref "U104") (pin "2") (pinfunction "DO_2") (pintype "unspecified"))
    )
    (net (code "62") (name "QSPI_SD2") (class "Default")
      (node (ref "U101") (pin "54") (pinfunction "QSPI_SD2_54") (pintype "bidirectional"))
      (node (ref "U104") (pin "3") (pinfunction "IO2_3") (pintype "unspecified"))
    )
    (net (code "63") (name "QSPI_SD3") (class "Default")
      (node (ref "U101") (pin "51") (pinfunction "QSPI_SD3_51") (pintype "bidirectional"))
      (node (ref "U104") (pin "7") (pinfunction "IO3_7") (pintype "unspecified"))
    )
    (net (code "64") (name "QSPI_SS") (class "Default")
      (node (ref "R124") (pin "2") (pinfunction "2_2") (pintype "input"))
      (node (ref "U101") (pin "56") (pinfunction "QSPI_SS_56") (pintype "bidirectional"))
      (node (ref "U104") (pin "1") (pinfunction "CS#_1") (pintype "unspecified"))
    )
    (net (code "65") (name "RESET_N") (class "Default")
      (node (ref "C127") (pin "2") (pinfunction "2_2") (pintype "unspecified"))
      (node (ref "R125") (pin "2") (pinfunction "2_2") (pintype "input"))
      (node (ref "U101") (pin "26") (pinfunction "RUN_26") (pintype "input"))
    )
    (net (code "66") (name "ROW0") (class "Default")
      (node (ref "D201") (pin "1") (pinfunction "K_1") (pintype "input"))
      (node (ref "D202") (pin "1") (pinfunction "K_1") (pintype "input"))
      (node (ref "D203") (pin "1") (pinfunction "K_1") (pintype "input"))
      (node (ref "R113") (pin "2") (pinfunction "2_2") (pintype "input"))
    )
    (net (code "67") (name "ROW0_R") (class "Default")
      (node (ref "C117") (pin "2") (pinfunction "2_2") (pintype "unspecified"))
      (node (ref "R113") (pin "1") (pinfunction "1_1") (pintype "input"))
      (node (ref "U101") (pin "11") (pinfunction "GPIO8_11") (pintype "bidirectional"))
    )
    (net (code "68") (name "ROW1") (class "Default")
      (node (ref "D204") (pin "1") (pinfunction "K_1") (pintype "input"))
      (node (ref "D205") (pin "1") (pinfunction "K_1") (pintype "input"))
      (node (ref "D206") (pin "1") (pinfunction "K_1") (pintype "input"))
      (node (ref "R114") (pin "2") (pinfunction "2_2") (pintype "input"))
    )
    (net (code "69") (name "ROW1_R") (class "Default")
      (node (ref "C120") (pin "2") (pinfunction "2_2") (pintype "unspecified"))
      (node (ref "R114") (pin "1") (pinfunction "1_1") (pintype "input"))
      (node (ref "U101") (pin "12") (pinfunction "GPIO9_12") (pintype "bidirectional"))
    )
    (net (code "70") (name "ROW2") (class "Default")
      (node (ref "D207") (pin "1") (pinfunction "K_1") (pintype "input"))
      (node (ref "D208") (pin "1") (pinfunction "K_1") (pintype "input"))
      (node (ref "D209") (pin "1") (pinfunction "K_1") (pintype "input"))
      (node (ref "R115") (pin "2") (pinfunction "2_2") (pintype "input"))
    )
    (net (code "71") (name "ROW2_R") (class "Default")
      (node (ref "C121") (pin "2") (pinfunction "2_2") (pintype "unspecified"))
      (node (ref "R115") (pin "1") (pinfunction "1_1") (pintype "input"))
      (node (ref "U101") (pin "13") (pinfunction "GPIO10_13") (pintype "bidirectional"))
    )
    (net (code "72") (name "ROW3") (class "Default")
      (node (ref "D210") (pin "1") (pinfunction "K_1") (pintype "input"))
      (node (ref "D211") (pin "1") (pinfunction "K_1") (pintype "input"))
      (node (ref "D212") (pin "1") (pinfunction "K_1") (pintype "input"))
      (node (ref "R116") (pin "2") (pinfunction "2_2") (pintype "input"))
    )
    (net (code "73") (name "ROW3_R") (class "Default")
      (node (ref "C122") (pin "2") (pinfunction "2_2") (pintype "unspecified"))
      (node (ref "R116") (pin "1") (pinfunction "1_1") (pintype "input"))
      (node (ref "U101") (pin "14") (pinfunction "GPIO11_14") (pintype "bidirectional"))
    )
    (net (code "74") (name "SWCLK") (class "Default")
      (node (ref "J102") (pin "1") (pinfunction "1_1") (pintype "input"))
      (node (ref "U101") (pin "24") (pinfunction "SWCLK_24") (pintype "output"))
    )
    (net (code "75") (name "SWDIO") (class "Default")
      (node (ref "J102") (pin "3") (pinfunction "3_3") (pintype "input"))
      (node (ref "U101") (pin "25") (pinfunction "SWD_25") (pintype "bidirectional"))
    )
    (net (code "76") (name "USB_N") (class "Default")
      (node (ref "R109") (pin "2") (pinfunction "2_2") (pintype "input"))
      (node (ref "U101") (pin "46") (pinfunction "USB_DM_46") (pintype "bidirectional"))
    )
    (net (code "77") (name "USB_P") (class "Default")
      (node (ref "R111") (pin "2") (pinfunction "2_2") (pintype "input"))
      (node (ref "U101") (pin "47") (pinfunction "USB_DP_47") (pintype "bidirectional"))
    )
    (net (code "78") (name "USER_LED1") (class "Default")
      (node (ref "R103") (pin "2") (pinfunction "2_2") (pintype "input"))
      (node (ref "U101") (pin "37") (pinfunction "GPIO25_37") (pintype "bidirectional"))
    )
    (net (code "79") (name "USER_LED2_B") (class "Default")
      (node (ref "R107") (pin "2") (pinfunction "2_2") (pintype "input"))
      (node (ref "U101") (pin "40") (pinfunction "GPIO28_ADC2_40") (pintype "bidirectional"))
    )
    (net (code "80") (name "USER_LED2_G") (class "Default")
      (node (ref "R106") (pin "2") (pinfunction "2_2") (pintype "input"))
      (node (ref "U101") (pin "39") (pinfunction "GPIO27_ADC1_39") (pintype "bidirectional"))
    )
    (net (code "81") (name "USER_LED2_R") (class "Default")
      (node (ref "R105") (pin "2") (pinfunction "2_2") (pintype "input"))
      (node (ref "U101") (pin "38") (pinfunction "GPIO26_ADC0_38") (pintype "bidirectional"))
    )
    (net (code "82") (name "XIN") (class "Default")
      (node (ref "C123") (pin "1") (pinfunction "1_1") (pintype "unspecified"))
      (node (ref "R120") (pin "2") (pinfunction "2_2") (pintype "input"))
      (node (ref "U101") (pin "20") (pinfunction "XIN_20") (pintype "input"))
      (node (ref "Y101") (pin "1") (pinfunction "1_1") (pintype "input"))
    )
    (net (code "83") (name "XOUT") (class "Default")
      (node (ref "R120") (pin "1") (pinfunction "1_1") (pintype "input"))
      (node (ref "R121") (pin "2") (pinfunction "2_2") (pintype "input"))
      (node (ref "U101") (pin "21") (pinfunction "XOUT_21") (pintype "unspecified"))
    )
    (net (code "84") (name "X_R") (class "Default")
      (node (ref "C124") (pin "1") (pinfunction "1_1") (pintype "unspecified"))
      (node (ref "R121") (pin "1") (pinfunction "1_1") (pintype "input"))
      (node (ref "Y101") (pin "3") (pinfunction "3_3") (pintype "input"))
    )
    (net (code "85") (name "unconnected-(J101-SBU1-Pad9)") (class "Default")
      (node (ref "J101") (pin "9") (pinfunction "SBU1_9") (pintype "unspecified+no_connect"))
    )
    (net (code "86") (name "unconnected-(J101-SBU2-Pad3)") (class "Default")
      (node (ref "J101") (pin "3") (pinfunction "SBU2_3") (pintype "unspecified+no_connect"))
    )
    (net (code "87") (name "unconnected-(LED209-DOUT-Pad2)") (class "Default")
      (node (ref "LED209") (pin "2") (pinfunction "DOUT_2") (pintype "unspecified+no_connect"))
    )
    (net (code "88") (name "unconnected-(U101-GPIO3-Pad5)") (class "Default")
      (node (ref "U101") (pin "5") (pinfunction "GPIO3_5") (pintype "bidirectional+no_connect"))
    )
    (net (code "89") (name "unconnected-(U101-GPIO4-Pad6)") (class "Default")
      (node (ref "U101") (pin "6") (pinfunction "GPIO4_6") (pintype "bidirectional+no_connect"))
    )
    (net (code "90") (name "unconnected-(U101-GPIO5-Pad7)") (class "Default")
      (node (ref "U101") (pin "7") (pinfunction "GPIO5_7") (pintype "bidirectional+no_connect"))
    )
    (net (code "91") (name "unconnected-(U101-GPIO6-Pad8)") (class "Default")
      (node (ref "U101") (pin "8") (pinfunction "GPIO6_8") (pintype "bidirectional+no_connect"))
    )
    (net (code "92") (name "unconnected-(U101-GPIO7-Pad9)") (class "Default")
      (node (ref "U101") (pin "9") (pinfunction "GPIO7_9") (pintype "bidirectional+no_connect"))
    )
    (net (code "93") (name "unconnected-(U101-GPIO12-Pad15)") (class "Default")
      (node (ref "U101") (pin "15") (pinfunction "GPIO12_15") (pintype "bidirectional+no_connect"))
    )
    (net (code "94") (name "unconnected-(U101-GPIO13-Pad16)") (class "Default")
      (node (ref "U101") (pin "16") (pinfunction "GPIO13_16") (pintype "bidirectional+no_connect"))
    )
    (net (code "95") (name "unconnected-(U101-GPIO14-Pad17)") (class "Default")
      (node (ref "U101") (pin "17") (pinfunction "GPIO14_17") (pintype "bidirectional+no_connect"))
    )
    (net (code "96") (name "unconnected-(U101-GPIO21-Pad32)") (class "Default")
      (node (ref "U101") (pin "32") (pinfunction "GPIO21_32") (pintype "bidirectional+no_connect"))
    )
    (net (code "97") (name "unconnected-(U101-GPIO22-Pad34)") (class "Default")
      (node (ref "U101") (pin "34") (pinfunction "GPIO22_34") (pintype "bidirectional+no_connect"))
    )
    (net (code "98") (name "unconnected-(U101-GPIO23-Pad35)") (class "Default")
      (node (ref "U101") (pin "35") (pinfunction "GPIO23_35") (pintype "bidirectional+no_connect"))
    )
    (net (code "99") (name "unconnected-(U101-GPIO29_ADC3-Pad41)") (class "Default")
      (node (ref "U101") (pin "41") (pinfunction "GPIO29_ADC3_41") (pintype "bidirectional+no_connect"))
    )
  )
)
